# 02_INTERFACE.net
KiCad netlist of a schematic drawn in Altium Designer
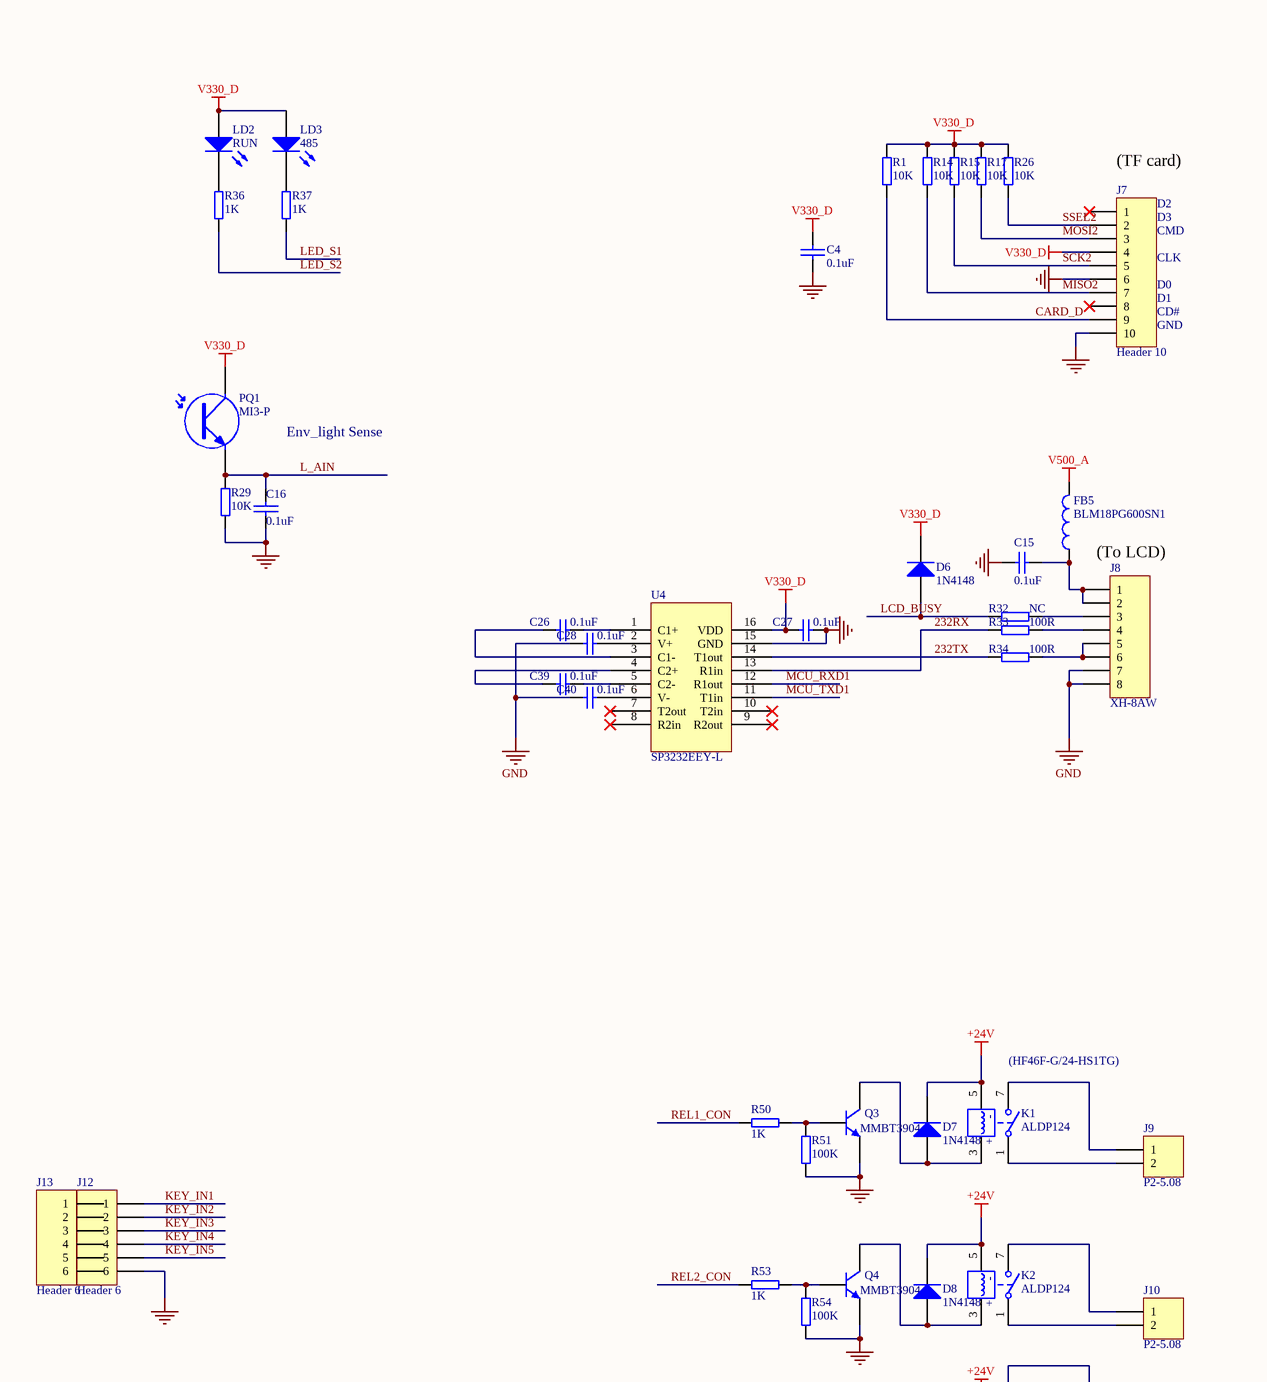
[diagram p0: 02_INTERFACE.SchDoc, top left]
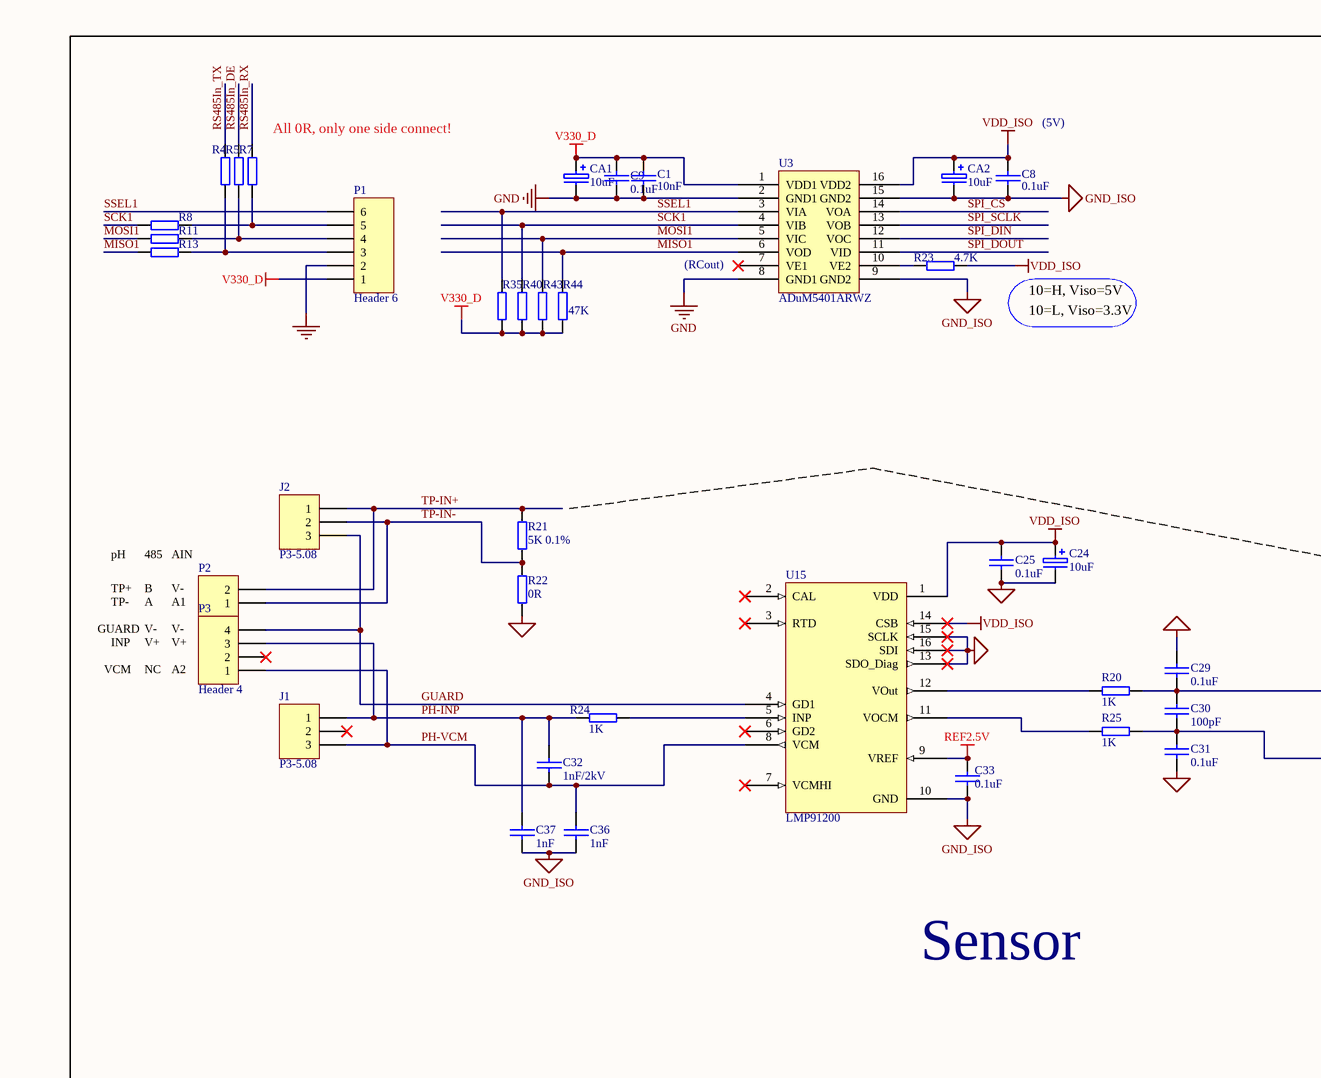
[diagram p1: 02_INTERFACE.SchDoc, top middle]
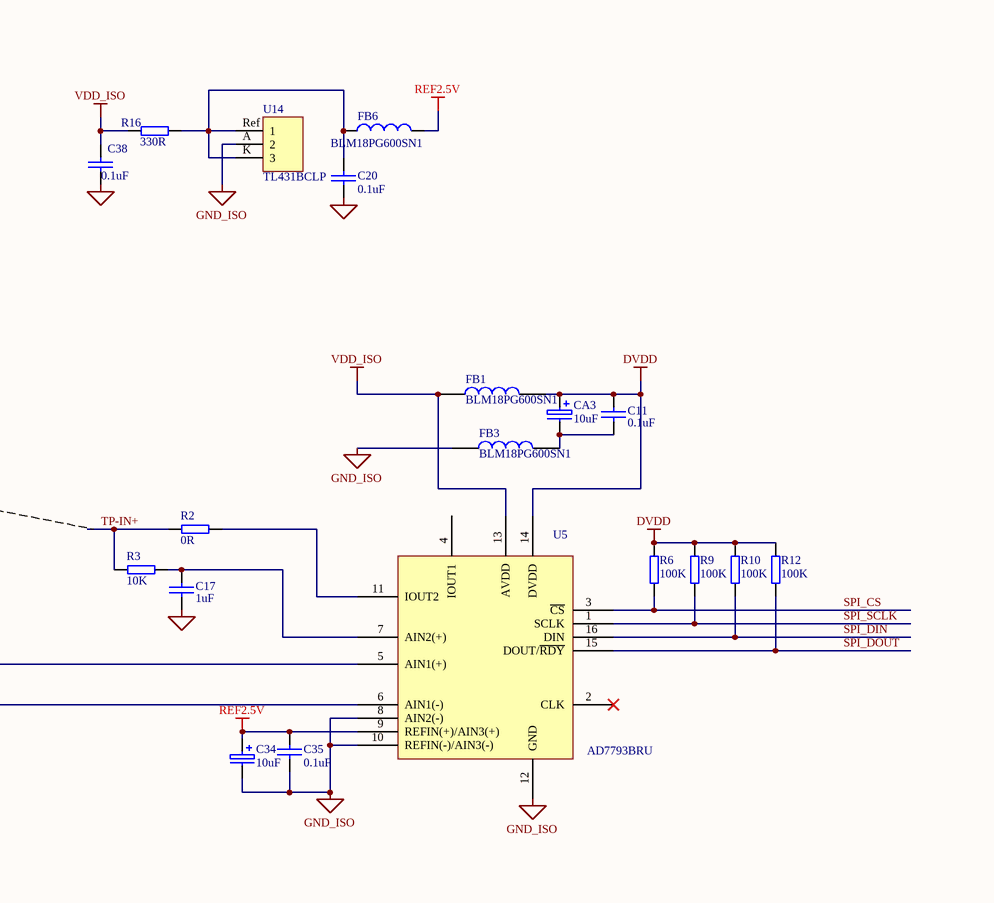
[diagram p2: 02_INTERFACE.SchDoc, top right]
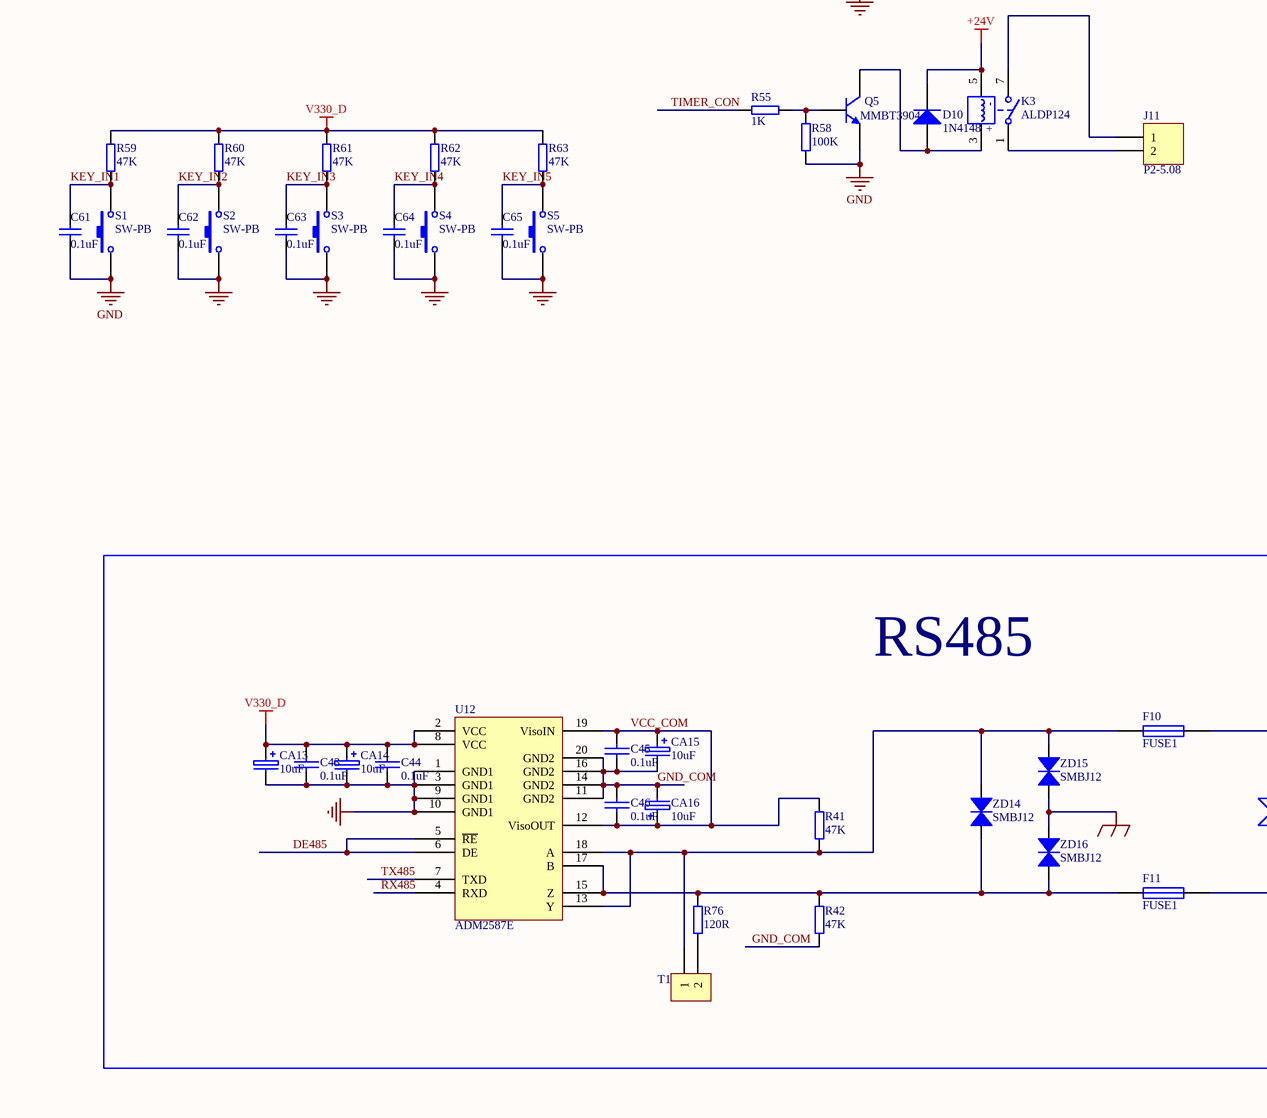
[diagram p3: 02_INTERFACE.SchDoc, bottom left]
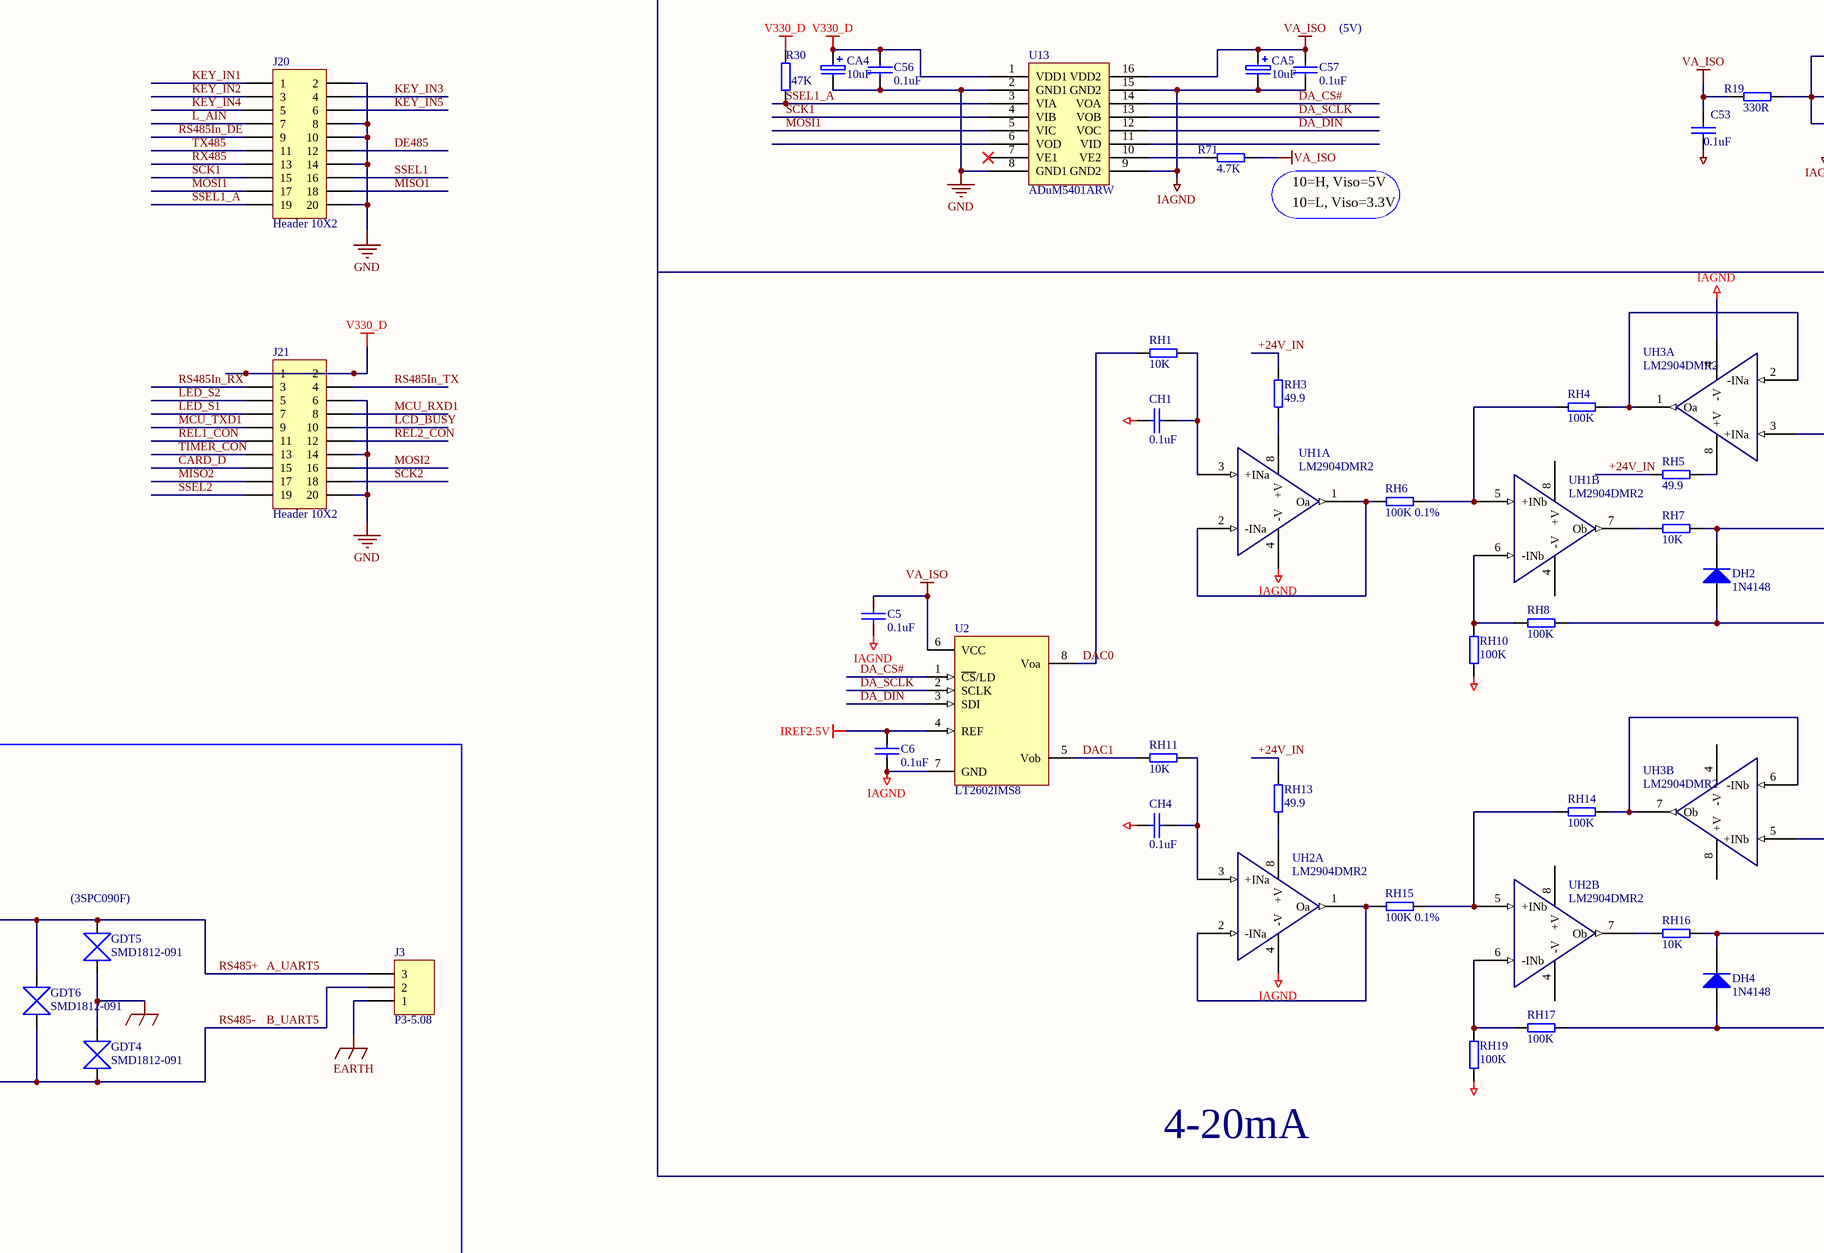
[diagram p4: 02_INTERFACE.SchDoc, bottom middle]
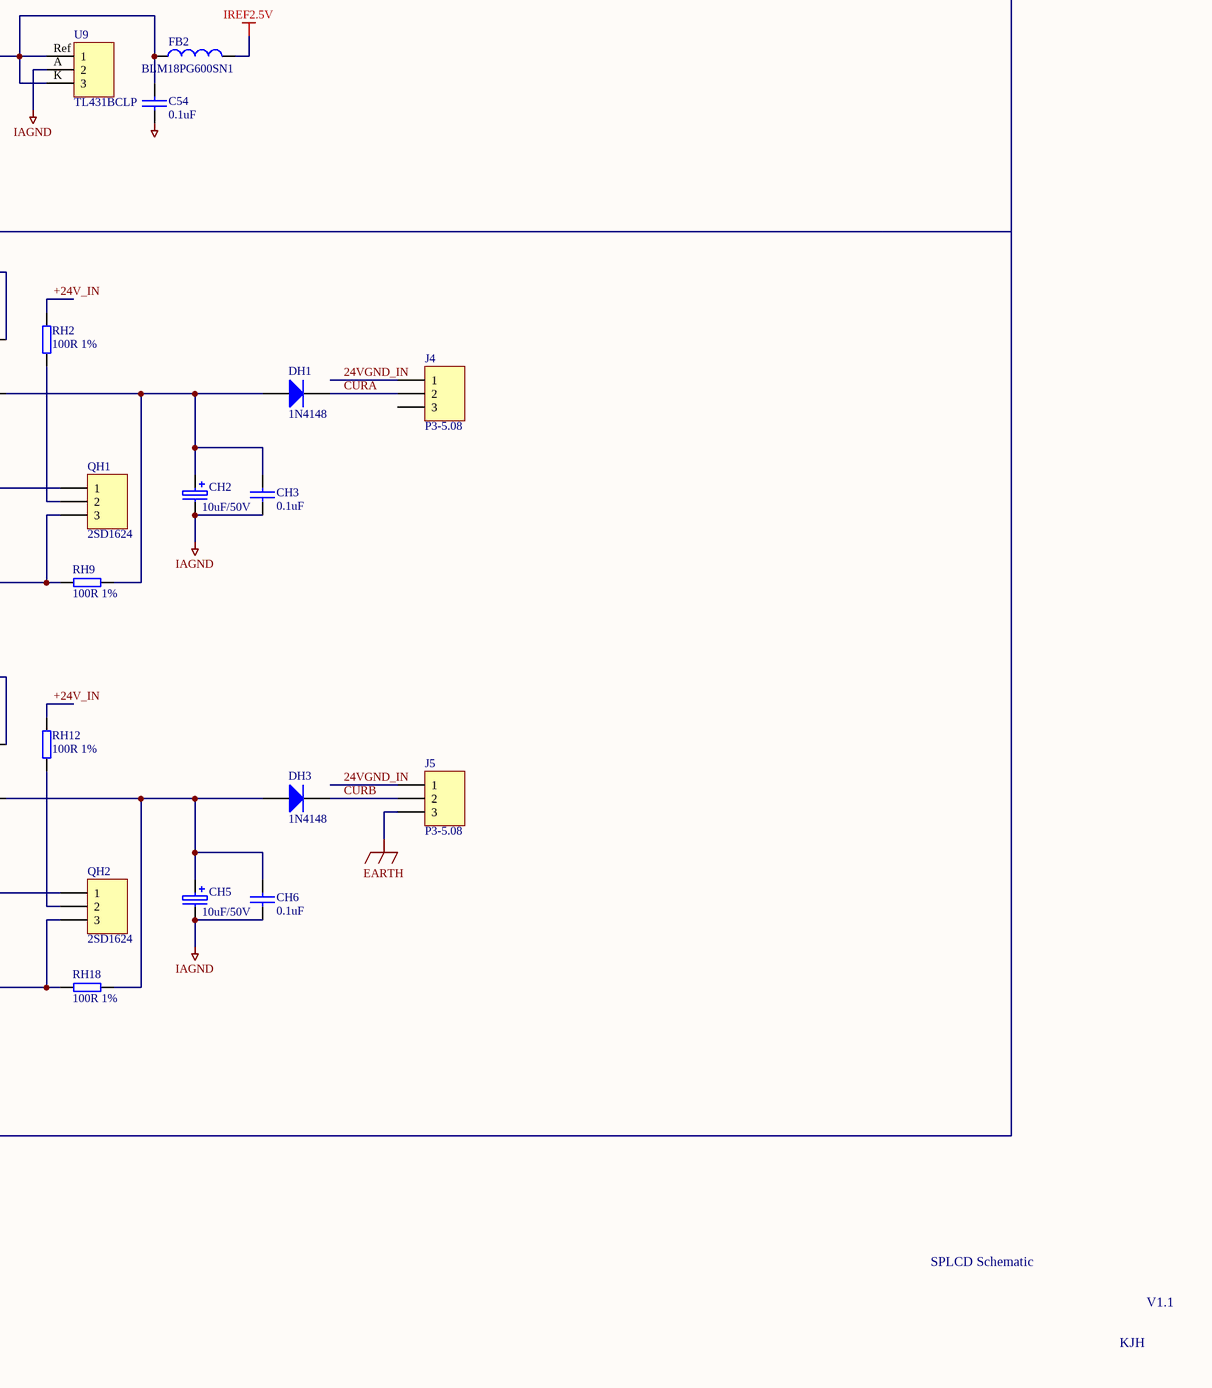
[diagram p5: 02_INTERFACE.SchDoc, bottom right]

(export (version "E")
  (design (tool "Eeschema 10.0.6"))
  (components
    (comp (ref "C1")
      (value "10nF")
      (footprint "0603A")
      (description "电容")
      (libsource (lib "") (part "CAP_1"))
    )
    (comp (ref "C4")
      (value "0.1uF")
      (footprint "0603A")
      (description "Capacitor")
      (libsource (lib "*") (part "CAP"))
    )
    (comp (ref "C5")
      (value "0.1uF")
      (footprint "0603A")
      (description "Capacitor")
      (libsource (lib "*") (part "CAP"))
    )
    (comp (ref "C6")
      (value "0.1uF")
      (footprint "0603A")
      (description "Capacitor")
      (libsource (lib "*") (part "CAP"))
    )
    (comp (ref "C8")
      (value "0.1uF")
      (footprint "0603A")
      (description "电容")
      (libsource (lib "") (part "CAP_1"))
    )
    (comp (ref "C9")
      (value "0.1uF")
      (footprint "0603A")
      (description "电容")
      (libsource (lib "") (part "CAP_1"))
    )
    (comp (ref "C11")
      (value "0.1uF")
      (footprint "0603A")
      (description "电容")
      (libsource (lib "") (part "CAP_1"))
    )
    (comp (ref "C15")
      (value "0.1uF")
      (footprint "0603A")
      (description "Capacitor, X7R Ceramic")
      (libsource (lib "Miscellaneous Devices") (part "Cap"))
    )
    (comp (ref "C16")
      (value "0.1uF")
      (footprint "0603")
      (description "Capacitor")
      (libsource (lib "*") (part "CAP"))
    )
    (comp (ref "C17")
      (value "1uF")
      (footprint "0603A")
      (description "电容")
      (libsource (lib "") (part "CAP_1"))
    )
    (comp (ref "C20")
      (value "0.1uF")
      (footprint "0603A")
      (description "Capacitor")
      (libsource (lib "*") (part "CAP"))
    )
    (comp (ref "C24")
      (value "10uF")
      (footprint "1206")
      (description "极性电容")
      (libsource (lib "*") (part "CAPE"))
    )
    (comp (ref "C25")
      (value "0.1uF")
      (footprint "0603A")
      (description "Capacitor")
      (libsource (lib "*") (part "CAP"))
    )
    (comp (ref "C26")
      (value "0.1uF")
      (footprint "0603A")
      (description "'Capacitor, X7R Ceramic")
      (libsource (lib "Miscellaneous Devices") (part "Cap"))
    )
    (comp (ref "C27")
      (value "0.1uF")
      (footprint "0603A")
      (description "'Capacitor, X7R Ceramic")
      (libsource (lib "Miscellaneous Devices") (part "Cap"))
    )
    (comp (ref "C28")
      (value "0.1uF")
      (footprint "0603A")
      (description "'Capacitor, X7R Ceramic")
      (libsource (lib "Miscellaneous Devices") (part "Cap"))
    )
    (comp (ref "C29")
      (value "0.1uF")
      (footprint "0603A")
      (description "Capacitor")
      (libsource (lib "*") (part "CAP"))
    )
    (comp (ref "C30")
      (value "100pF")
      (footprint "0603A")
      (description "Capacitor")
      (libsource (lib "*") (part "CAP"))
    )
    (comp (ref "C31")
      (value "0.1uF")
      (footprint "0603A")
      (description "Capacitor")
      (libsource (lib "*") (part "CAP"))
    )
    (comp (ref "C32")
      (value "1nF/2kV")
      (footprint "RAD-0.2")
      (description "Capacitor")
      (libsource (lib "*") (part "CAP"))
    )
    (comp (ref "C33")
      (value "0.1uF")
      (footprint "0603A")
      (description "Capacitor")
      (libsource (lib "*") (part "CAP"))
    )
    (comp (ref "C34")
      (value "10uF")
      (footprint "1206")
      (description "极性电容")
      (libsource (lib "*") (part "CAPE"))
    )
    (comp (ref "C35")
      (value "0.1uF")
      (footprint "0603A")
      (description "Capacitor")
      (libsource (lib "*") (part "CAP"))
    )
    (comp (ref "C36")
      (value "1nF")
      (footprint "0603A")
      (description "Capacitor")
      (libsource (lib "*") (part "CAP"))
    )
    (comp (ref "C37")
      (value "1nF")
      (footprint "0603A")
      (description "Capacitor")
      (libsource (lib "*") (part "CAP"))
    )
    (comp (ref "C38")
      (value "0.1uF")
      (footprint "0603A")
      (description "Capacitor")
      (libsource (lib "*") (part "CAP"))
    )
    (comp (ref "C39")
      (value "0.1uF")
      (footprint "0603A")
      (description "'Capacitor, X7R Ceramic")
      (libsource (lib "Miscellaneous Devices") (part "Cap"))
    )
    (comp (ref "C40")
      (value "0.1uF")
      (footprint "0603A")
      (description "'Capacitor, X7R Ceramic")
      (libsource (lib "Miscellaneous Devices") (part "Cap"))
    )
    (comp (ref "C43")
      (value "0.1uF")
      (footprint "0603")
      (description "电容")
      (libsource (lib "") (part "CAP_1"))
    )
    (comp (ref "C44")
      (value "0.1uF")
      (footprint "0603")
      (description "电容")
      (libsource (lib "") (part "CAP_1"))
    )
    (comp (ref "C45")
      (value "0.1uF")
      (footprint "0603")
      (description "电容")
      (libsource (lib "") (part "CAP_1"))
    )
    (comp (ref "C46")
      (value "0.1uF")
      (footprint "0603")
      (description "电容")
      (libsource (lib "") (part "CAP_1"))
    )
    (comp (ref "C53")
      (value "0.1uF")
      (footprint "0603A")
      (description "Capacitor")
      (libsource (lib "*") (part "CAP"))
    )
    (comp (ref "C54")
      (value "0.1uF")
      (footprint "0603A")
      (description "Capacitor")
      (libsource (lib "*") (part "CAP"))
    )
    (comp (ref "C56")
      (value "0.1uF")
      (footprint "0603A")
      (description "Capacitor")
      (libsource (lib "*") (part "CAP"))
    )
    (comp (ref "C57")
      (value "0.1uF")
      (footprint "0603A")
      (description "Capacitor")
      (libsource (lib "*") (part "CAP"))
    )
    (comp (ref "C61")
      (value "0.1uF")
      (footprint "0603A")
      (description "Capacitor, X7R Ceramic")
      (libsource (lib "Miscellaneous Devices") (part "Cap"))
    )
    (comp (ref "C62")
      (value "0.1uF")
      (footprint "0603A")
      (description "Capacitor, X7R Ceramic")
      (libsource (lib "Miscellaneous Devices") (part "Cap"))
    )
    (comp (ref "C63")
      (value "0.1uF")
      (footprint "0603A")
      (description "Capacitor, X7R Ceramic")
      (libsource (lib "Miscellaneous Devices") (part "Cap"))
    )
    (comp (ref "C64")
      (value "0.1uF")
      (footprint "0603A")
      (description "Capacitor, X7R Ceramic")
      (libsource (lib "Miscellaneous Devices") (part "Cap"))
    )
    (comp (ref "C65")
      (value "0.1uF")
      (footprint "0603A")
      (description "Capacitor, X7R Ceramic")
      (libsource (lib "Miscellaneous Devices") (part "Cap"))
    )
    (comp (ref "CA1")
      (value "10uF")
      (footprint "1206")
      (description "极性电容")
      (libsource (lib "*") (part "CAPE"))
    )
    (comp (ref "CA2")
      (value "10uF")
      (footprint "1206")
      (description "极性电容")
      (libsource (lib "*") (part "CAPE"))
    )
    (comp (ref "CA3")
      (value "10uF")
      (footprint "1206")
      (description "极性电容")
      (libsource (lib "*") (part "CAPE"))
    )
    (comp (ref "CA4")
      (value "10uF")
      (footprint "1206")
      (description "极性电容")
      (libsource (lib "*") (part "CAPE"))
    )
    (comp (ref "CA5")
      (value "10uF")
      (footprint "1206C")
      (description "极性电容")
      (libsource (lib "*") (part "CAPE"))
    )
    (comp (ref "CA13")
      (value "10uF")
      (footprint "1206C")
      (description "极性电容")
      (libsource (lib "*") (part "CAPE"))
    )
    (comp (ref "CA14")
      (value "10uF")
      (footprint "1206C")
      (description "极性电容")
      (libsource (lib "*") (part "CAPE"))
    )
    (comp (ref "CA15")
      (value "10uF")
      (footprint "1206C")
      (description "极性电容")
      (libsource (lib "*") (part "CAPE"))
    )
    (comp (ref "CA16")
      (value "10uF")
      (footprint "1206C")
      (description "极性电容")
      (libsource (lib "*") (part "CAPE"))
    )
    (comp (ref "CH1")
      (value "0.1uF")
      (footprint "0603A")
      (description "Capacitor")
      (libsource (lib "*") (part "CAP"))
    )
    (comp (ref "CH2")
      (value "10uF/50V")
      (footprint "1206")
      (description "极性电容")
      (libsource (lib "*") (part "CAPE"))
    )
    (comp (ref "CH3")
      (value "0.1uF")
      (footprint "0603A")
      (description "Capacitor")
      (libsource (lib "*") (part "CAP"))
    )
    (comp (ref "CH4")
      (value "0.1uF")
      (footprint "0603A")
      (description "Capacitor")
      (libsource (lib "*") (part "CAP"))
    )
    (comp (ref "CH5")
      (value "10uF/50V")
      (footprint "1206")
      (description "极性电容")
      (libsource (lib "*") (part "CAPE"))
    )
    (comp (ref "CH6")
      (value "0.1uF")
      (footprint "0603A")
      (description "Capacitor")
      (libsource (lib "*") (part "CAP"))
    )
    (comp (ref "D6")
      (value "1N4148")
      (footprint "1206")
      (description "High Conductance Fast Diode")
      (fields (field (name "PUBLISHER") "Altium Limited"))
      (libsource (lib "Miscellaneous Devices") (part "Diode 1N4148"))
    )
    (comp (ref "D7")
      (value "1N4148")
      (footprint "1206")
      (description "High Conductance Fast Diode")
      (fields (field (name "PUBLISHER") "Altium Limited"))
      (libsource (lib "Miscellaneous Devices") (part "Diode 1N4148"))
    )
    (comp (ref "D8")
      (value "1N4148")
      (footprint "1206")
      (description "High Conductance Fast Diode")
      (fields (field (name "PUBLISHER") "Altium Limited"))
      (libsource (lib "Miscellaneous Devices") (part "Diode 1N4148"))
    )
    (comp (ref "D10")
      (value "1N4148")
      (footprint "1206")
      (description "High Conductance Fast Diode")
      (fields (field (name "PUBLISHER") "Altium Limited"))
      (libsource (lib "Miscellaneous Devices") (part "Diode 1N4148"))
    )
    (comp (ref "DH1")
      (value "1N4148")
      (footprint "1206D")
      (description "1 Amp General Purpose Rectifier")
      (fields (field (name "PUBLISHER") "Altium Limited"))
      (libsource (lib "Miscellaneous Devices") (part "Diode 1N4001"))
    )
    (comp (ref "DH2")
      (value "1N4148")
      (footprint "1206D")
      (description "1 Amp General Purpose Rectifier")
      (fields (field (name "PUBLISHER") "Altium Limited"))
      (libsource (lib "Miscellaneous Devices") (part "Diode 1N4001"))
    )
    (comp (ref "DH3")
      (value "1N4148")
      (footprint "1206D")
      (description "1 Amp General Purpose Rectifier")
      (fields (field (name "PUBLISHER") "Altium Limited"))
      (libsource (lib "Miscellaneous Devices") (part "Diode 1N4001"))
    )
    (comp (ref "DH4")
      (value "1N4148")
      (footprint "1206D")
      (description "1 Amp General Purpose Rectifier")
      (fields (field (name "PUBLISHER") "Altium Limited"))
      (libsource (lib "Miscellaneous Devices") (part "Diode 1N4001"))
    )
    (comp (ref "F10")
      (value "FUSE1")
      (footprint "1206")
      (description "Fuse")
      (libsource (lib "*") (part "FUSE1"))
    )
    (comp (ref "F11")
      (value "FUSE1")
      (footprint "1206")
      (description "Fuse")
      (libsource (lib "*") (part "FUSE1"))
    )
    (comp (ref "FB1") (value "BLM18PG600SN1") (footprint "0603A") (libsource (lib "*") (part "INDUCTOR")))
    (comp (ref "FB2")
      (value "BLM18PG600SN1")
      (footprint "0603A")
      (description "Inductor")
      (fields (field (name "PUBLISHER") "Altium Limited"))
      (libsource (lib "Miscellaneous Devices") (part "Inductor"))
    )
    (comp (ref "FB3") (value "BLM18PG600SN1") (footprint "0603A") (libsource (lib "*") (part "INDUCTOR")))
    (comp (ref "FB5")
      (value "BLM18PG600SN1")
      (footprint "0603A")
      (description "Inductor")
      (fields (field (name "PUBLISHER") "Altium Limited"))
      (libsource (lib "Miscellaneous Devices") (part "Inductor"))
    )
    (comp (ref "FB6")
      (value "BLM18PG600SN1")
      (footprint "0603A")
      (description "Inductor")
      (fields (field (name "PUBLISHER") "Altium Limited"))
      (libsource (lib "Miscellaneous Devices") (part "Inductor"))
    )
    (comp (ref "GDT4") (value "SMD1812-091") (footprint "1812") (libsource (lib "*") (part "BT90")))
    (comp (ref "GDT5") (value "SMD1812-091") (footprint "1812") (libsource (lib "*") (part "BT90")))
    (comp (ref "GDT6") (value "SMD1812-091") (footprint "1812") (libsource (lib "*") (part "BT90")))
    (comp (ref "J1")
      (value "P3-5.08")
      (footprint "PH3-5.08mm")
      (description "Header, 3-Pin")
      (fields (field (name "PUBLISHER") "Altium Limited"))
      (libsource (lib "Miscellaneous Connectors") (part "Header 3"))
    )
    (comp (ref "J2")
      (value "P3-5.08")
      (footprint "PH3-5.08mm")
      (description "Header, 3-Pin")
      (fields (field (name "PUBLISHER") "Altium Limited"))
      (libsource (lib "Miscellaneous Connectors") (part "Header 3"))
    )
    (comp (ref "J3")
      (value "P3-5.08")
      (footprint "PH3-5.08mm")
      (description "Header, 3-Pin")
      (fields (field (name "PUBLISHER") "Altium Limited"))
      (libsource (lib "") (part "Header 3_2"))
    )
    (comp (ref "J4")
      (value "P3-5.08")
      (footprint "PH3-5.08mm")
      (description "Header, 3-Pin")
      (fields (field (name "PUBLISHER") "Altium Limited"))
      (libsource (lib "") (part "Header 3_1"))
    )
    (comp (ref "J5")
      (value "P3-5.08")
      (footprint "PH3-5.08mm")
      (description "Header, 3-Pin")
      (fields (field (name "PUBLISHER") "Altium Limited"))
      (libsource (lib "") (part "Header 3_1"))
    )
    (comp (ref "J7")
      (value "Header 10")
      (footprint "TF Socket")
      (description "Header, 10-Pin")
      (fields (field (name "PUBLISHER") "Altium Limited"))
      (libsource (lib "Miscellaneous Connectors") (part "Header 10"))
    )
    (comp (ref "J8")
      (value "XH-8AW")
      (footprint "HDR1X8")
      (description "Header, 8-Pin")
      (fields (field (name "PUBLISHER") "Altium Limited"))
      (libsource (lib "Miscellaneous Connectors") (part "Header 8"))
    )
    (comp (ref "J9")
      (value "P2-5.08")
      (footprint "PH2-5.08mm")
      (description "Header, 2-Pin")
      (fields (field (name "PUBLISHER") "Altium Limited"))
      (libsource (lib "Miscellaneous Connectors") (part "Header 2"))
    )
    (comp (ref "J10")
      (value "P2-5.08")
      (footprint "PH2-5.08mm")
      (description "Header, 2-Pin")
      (fields (field (name "PUBLISHER") "Altium Limited"))
      (libsource (lib "Miscellaneous Connectors") (part "Header 2"))
    )
    (comp (ref "J11")
      (value "P2-5.08")
      (footprint "PH2-5.08mm")
      (description "Header, 2-Pin")
      (fields (field (name "PUBLISHER") "Altium Limited"))
      (libsource (lib "Miscellaneous Connectors") (part "Header 2"))
    )
    (comp (ref "J12")
      (value "Header 6")
      (footprint "HDR1X6")
      (description "Header, 6-Pin")
      (fields (field (name "PUBLISHER") "Altium Limited"))
      (libsource (lib "Miscellaneous Connectors") (part "Header 6"))
    )
    (comp (ref "J13")
      (value "Header 6")
      (footprint "HDR1X6")
      (description "Header, 6-Pin")
      (fields (field (name "PUBLISHER") "Altium Limited"))
      (libsource (lib "Miscellaneous Connectors") (part "Header 6"))
    )
    (comp (ref "J20")
      (value "Header 10X2")
      (footprint "HDR2X10")
      (description "Header, 10-Pin, Dual row")
      (fields (field (name "PUBLISHER") "Altium Limited"))
      (libsource (lib "Miscellaneous Connectors") (part "Header 10X2"))
    )
    (comp (ref "J21")
      (value "Header 10X2")
      (footprint "HDR2X10")
      (description "Header, 10-Pin, Dual row")
      (fields (field (name "PUBLISHER") "Altium Limited"))
      (libsource (lib "Miscellaneous Connectors") (part "Header 10X2"))
    )
    (comp (ref "K1")
      (value "ALDP124")
      (footprint "ALDP124")
      (description "24V coil, 5A SPST Relay")
      (libsource (lib "S1A120000_COSMO") (part "S1A120000"))
    )
    (comp (ref "K2")
      (value "ALDP124")
      (footprint "ALDP124")
      (description "24V coil, 5A SPST Relay")
      (libsource (lib "S1A120000_COSMO") (part "S1A120000"))
    )
    (comp (ref "K3")
      (value "ALDP124")
      (footprint "ALDP124")
      (description "24V coil, 5A SPST Relay")
      (libsource (lib "S1A120000_COSMO") (part "S1A120000"))
    )
    (comp (ref "LD2")
      (value "RUN")
      (footprint "LED")
      (description "Typical INFRARED GaAs LED")
      (fields (field (name "PUBLISHER") "Altium Limited"))
      (libsource (lib "Miscellaneous Devices") (part "LED0"))
    )
    (comp (ref "LD3")
      (value "485")
      (footprint "LED")
      (description "Typical INFRARED GaAs LED")
      (fields (field (name "PUBLISHER") "Altium Limited"))
      (libsource (lib "Miscellaneous Devices") (part "LED0"))
    )
    (comp (ref "P1")
      (value "Header 6")
      (footprint "HDR1X6")
      (description "Header, 6-Pin")
      (fields (field (name "PUBLISHER") "Altium Limited"))
      (libsource (lib "") (part "Header 6_1"))
    )
    (comp (ref "P2")
      (value "Header 2")
      (footprint "HDR1X2")
      (description "Header, 2-Pin")
      (fields (field (name "PUBLISHER") "Altium Limited"))
      (libsource (lib "") (part "Header 2_1"))
    )
    (comp (ref "P3")
      (value "Header 4")
      (footprint "HDR1X4")
      (description "Header, 4-Pin")
      (fields (field (name "PUBLISHER") "Altium Limited"))
      (libsource (lib "Miscellaneous Connectors") (part "Header 4"))
    )
    (comp (ref "PQ1")
      (value "MI3-P")
      (footprint "LED")
      (description "NPN Phototransistor")
      (fields (field (name "PUBLISHER") "Altium Limited"))
      (libsource (lib "Miscellaneous Devices") (part "Photo NPN"))
    )
    (comp (ref "Q3")
      (value "MMBT3904")
      (footprint "SOT23_N")
      (description "NPN Switching Transistor")
      (fields (field (name "PUBLISHER") "Altium Limited"))
      (libsource (lib "Philips Discrete BJT - Low Power") (part "MMBT3904"))
    )
    (comp (ref "Q4")
      (value "MMBT3904")
      (footprint "SOT23_N")
      (description "NPN Switching Transistor")
      (fields (field (name "PUBLISHER") "Altium Limited"))
      (libsource (lib "Philips Discrete BJT - Low Power") (part "MMBT3904"))
    )
    (comp (ref "Q5")
      (value "MMBT3904")
      (footprint "SOT23_N")
      (description "NPN Switching Transistor")
      (fields (field (name "PUBLISHER") "Altium Limited"))
      (libsource (lib "Philips Discrete BJT - Low Power") (part "MMBT3904"))
    )
    (comp (ref "QH1")
      (value "2SD1624")
      (footprint "SOT89M")
      (description "Header, 3-Pin")
      (fields (field (name "PUBLISHER") "Altium Limited"))
      (libsource (lib "") (part "Header 3_1"))
    )
    (comp (ref "QH2")
      (value "2SD1624")
      (footprint "SOT89M")
      (description "Header, 3-Pin")
      (fields (field (name "PUBLISHER") "Altium Limited"))
      (libsource (lib "") (part "Header 3_1"))
    )
    (comp (ref "R1") (value "10K") (footprint "0603A") (description "电阻") (libsource (lib "*") (part "RES")))
    (comp (ref "R2") (value "0R") (footprint "0603A") (description "电阻") (libsource (lib "*") (part "RES")))
    (comp (ref "R3") (value "10K") (footprint "0603A") (description "电阻") (libsource (lib "*") (part "RES")))
    (comp (ref "R4") (value "0R") (footprint "0603A") (description "电阻") (libsource (lib "*") (part "RES")))
    (comp (ref "R5") (value "0R") (footprint "0603A") (description "电阻") (libsource (lib "*") (part "RES")))
    (comp (ref "R6") (value "100K") (footprint "0603A") (description "电阻") (libsource (lib "*") (part "RES")))
    (comp (ref "R7") (value "0R") (footprint "0603A") (description "电阻") (libsource (lib "*") (part "RES")))
    (comp (ref "R8") (value "0R") (footprint "0603A") (description "电阻") (libsource (lib "*") (part "RES")))
    (comp (ref "R9") (value "100K") (footprint "0603A") (description "电阻") (libsource (lib "*") (part "RES")))
    (comp (ref "R10")
      (value "100K")
      (footprint "0603A")
      (description "电阻")
      (libsource (lib "*") (part "RES"))
    )
    (comp (ref "R11") (value "0R") (footprint "0603A") (description "电阻") (libsource (lib "*") (part "RES")))
    (comp (ref "R12")
      (value "100K")
      (footprint "0603A")
      (description "电阻")
      (libsource (lib "*") (part "RES"))
    )
    (comp (ref "R13") (value "0R") (footprint "0603A") (description "电阻") (libsource (lib "*") (part "RES")))
    (comp (ref "R14") (value "10K") (footprint "0603A") (description "电阻") (libsource (lib "*") (part "RES")))
    (comp (ref "R15") (value "10K") (footprint "0603A") (description "电阻") (libsource (lib "*") (part "RES")))
    (comp (ref "R16")
      (value "330R")
      (footprint "0603A")
      (description "电阻")
      (libsource (lib "*") (part "RES"))
    )
    (comp (ref "R17") (value "10K") (footprint "0603A") (description "电阻") (libsource (lib "*") (part "RES")))
    (comp (ref "R19")
      (value "330R")
      (footprint "0603A")
      (description "电阻")
      (libsource (lib "*") (part "RES"))
    )
    (comp (ref "R20") (value "1K") (footprint "0603A") (description "电阻") (libsource (lib "*") (part "RES")))
    (comp (ref "R21")
      (value "5K 0.1%")
      (footprint "0603A")
      (description "电阻")
      (libsource (lib "*") (part "RES"))
    )
    (comp (ref "R22") (value "0R") (footprint "0603A") (description "电阻") (libsource (lib "*") (part "RES")))
    (comp (ref "R23")
      (value "4.7K")
      (footprint "0603A")
      (description "电阻")
      (libsource (lib "*") (part "RES"))
    )
    (comp (ref "R24") (value "1K") (footprint "0603A") (description "电阻") (libsource (lib "*") (part "RES")))
    (comp (ref "R25") (value "1K") (footprint "0603A") (description "电阻") (libsource (lib "*") (part "RES")))
    (comp (ref "R26") (value "10K") (footprint "0603A") (description "电阻") (libsource (lib "*") (part "RES")))
    (comp (ref "R29") (value "10K") (footprint "0603A") (description "电阻") (libsource (lib "*") (part "RES")))
    (comp (ref "R30") (value "47K") (footprint "0603A") (description "电阻") (libsource (lib "*") (part "RES")))
    (comp (ref "R32") (value "NC") (footprint "0603A") (description "电阻") (libsource (lib "*") (part "RES")))
    (comp (ref "R33")
      (value "100R")
      (footprint "0603A")
      (description "电阻")
      (libsource (lib "*") (part "RES"))
    )
    (comp (ref "R34")
      (value "100R")
      (footprint "0603A")
      (description "电阻")
      (libsource (lib "*") (part "RES"))
    )
    (comp (ref "R35") (value "47K") (footprint "0603A") (description "电阻") (libsource (lib "*") (part "RES")))
    (comp (ref "R36") (value "1K") (footprint "0603A") (description "电阻") (libsource (lib "*") (part "RES")))
    (comp (ref "R37") (value "1K") (footprint "0603A") (description "电阻") (libsource (lib "*") (part "RES")))
    (comp (ref "R40") (value "47K") (footprint "0603A") (description "电阻") (libsource (lib "*") (part "RES")))
    (comp (ref "R41") (value "47K") (footprint "0603") (description "电阻") (libsource (lib "*") (part "RES")))
    (comp (ref "R42") (value "47K") (footprint "0603") (description "电阻") (libsource (lib "*") (part "RES")))
    (comp (ref "R43") (value "47K") (footprint "0603A") (description "电阻") (libsource (lib "*") (part "RES")))
    (comp (ref "R44") (value "47K") (footprint "0603A") (description "电阻") (libsource (lib "*") (part "RES")))
    (comp (ref "R50") (value "1K") (footprint "0603A") (description "电阻") (libsource (lib "*") (part "RES")))
    (comp (ref "R51")
      (value "100K")
      (footprint "0603A")
      (description "电阻")
      (libsource (lib "*") (part "RES"))
    )
    (comp (ref "R53") (value "1K") (footprint "0603A") (description "电阻") (libsource (lib "*") (part "RES")))
    (comp (ref "R54")
      (value "100K")
      (footprint "0603A")
      (description "电阻")
      (libsource (lib "*") (part "RES"))
    )
    (comp (ref "R55") (value "1K") (footprint "0603A") (description "电阻") (libsource (lib "*") (part "RES")))
    (comp (ref "R58")
      (value "100K")
      (footprint "0603A")
      (description "电阻")
      (libsource (lib "*") (part "RES"))
    )
    (comp (ref "R59") (value "47K") (footprint "0603A") (description "电阻") (libsource (lib "*") (part "RES")))
    (comp (ref "R60") (value "47K") (footprint "0603A") (description "电阻") (libsource (lib "*") (part "RES")))
    (comp (ref "R61") (value "47K") (footprint "0603A") (description "电阻") (libsource (lib "*") (part "RES")))
    (comp (ref "R62") (value "47K") (footprint "0603A") (description "电阻") (libsource (lib "*") (part "RES")))
    (comp (ref "R63") (value "47K") (footprint "0603A") (description "电阻") (libsource (lib "*") (part "RES")))
    (comp (ref "R71")
      (value "4.7K")
      (footprint "0603A")
      (description "电阻")
      (libsource (lib "*") (part "RES"))
    )
    (comp (ref "R76") (value "120R") (footprint "0603") (description "电阻") (libsource (lib "*") (part "RES")))
    (comp (ref "RH1") (value "10K") (footprint "0603A") (description "电阻") (libsource (lib "*") (part "RES")))
    (comp (ref "RH2")
      (value "100R 1%")
      (footprint "0603A")
      (description "电阻")
      (libsource (lib "*") (part "RES"))
    )
    (comp (ref "RH3")
      (value "49.9")
      (footprint "0603A")
      (description "电阻")
      (libsource (lib "*") (part "RES"))
    )
    (comp (ref "RH4")
      (value "100K")
      (footprint "0603A")
      (description "电阻")
      (libsource (lib "*") (part "RES"))
    )
    (comp (ref "RH5")
      (value "49.9")
      (footprint "0603A")
      (description "电阻")
      (libsource (lib "*") (part "RES"))
    )
    (comp (ref "RH6")
      (value "100K 0.1%")
      (footprint "0603A")
      (description "电阻")
      (libsource (lib "*") (part "RES"))
    )
    (comp (ref "RH7")
      (value "10K")
      (footprint "0603A")
      (description "Resistor")
      (libsource (lib "*") (part "RES"))
    )
    (comp (ref "RH8")
      (value "100K")
      (footprint "0603A")
      (description "电阻")
      (libsource (lib "*") (part "RES"))
    )
    (comp (ref "RH9")
      (value "100R 1%")
      (footprint "0603A")
      (description "电阻")
      (libsource (lib "*") (part "RES"))
    )
    (comp (ref "RH10")
      (value "100K")
      (footprint "0603A")
      (description "电阻")
      (libsource (lib "*") (part "RES"))
    )
    (comp (ref "RH11")
      (value "10K")
      (footprint "0603A")
      (description "电阻")
      (libsource (lib "*") (part "RES"))
    )
    (comp (ref "RH12")
      (value "100R 1%")
      (footprint "0603A")
      (description "电阻")
      (libsource (lib "*") (part "RES"))
    )
    (comp (ref "RH13")
      (value "49.9")
      (footprint "0603A")
      (description "电阻")
      (libsource (lib "*") (part "RES"))
    )
    (comp (ref "RH14")
      (value "100K")
      (footprint "0603A")
      (description "电阻")
      (libsource (lib "*") (part "RES"))
    )
    (comp (ref "RH15")
      (value "100K 0.1%")
      (footprint "0603A")
      (description "电阻")
      (libsource (lib "*") (part "RES"))
    )
    (comp (ref "RH16")
      (value "10K")
      (footprint "0603A")
      (description "Resistor")
      (libsource (lib "*") (part "RES"))
    )
    (comp (ref "RH17")
      (value "100K")
      (footprint "0603A")
      (description "电阻")
      (libsource (lib "*") (part "RES"))
    )
    (comp (ref "RH18")
      (value "100R 1%")
      (footprint "0603A")
      (description "电阻")
      (libsource (lib "*") (part "RES"))
    )
    (comp (ref "RH19")
      (value "100K")
      (footprint "0603A")
      (description "电阻")
      (libsource (lib "*") (part "RES"))
    )
    (comp (ref "S1")
      (value "SW-PB")
      (description "Switch")
      (fields (field (name "PUBLISHER") "Altium Limited"))
      (libsource (lib "Miscellaneous Devices") (part "SW-PB"))
    )
    (comp (ref "S2")
      (value "SW-PB")
      (description "Switch")
      (fields (field (name "PUBLISHER") "Altium Limited"))
      (libsource (lib "Miscellaneous Devices") (part "SW-PB"))
    )
    (comp (ref "S3")
      (value "SW-PB")
      (description "Switch")
      (fields (field (name "PUBLISHER") "Altium Limited"))
      (libsource (lib "Miscellaneous Devices") (part "SW-PB"))
    )
    (comp (ref "S4")
      (value "SW-PB")
      (description "Switch")
      (fields (field (name "PUBLISHER") "Altium Limited"))
      (libsource (lib "Miscellaneous Devices") (part "SW-PB"))
    )
    (comp (ref "S5")
      (value "SW-PB")
      (description "Switch")
      (fields (field (name "PUBLISHER") "Altium Limited"))
      (libsource (lib "Miscellaneous Devices") (part "SW-PB"))
    )
    (comp (ref "T1")
      (value "~")
      (footprint "SIP2")
      (description "Connector")
      (libsource (lib "*") (part "CON2"))
    )
    (comp (ref "U2") (value "LT2602IMS8") (footprint "LT2602") (libsource (lib "SP1100RS") (part "LT2602")))
    (comp (ref "U3")
      (value "ADuM5401ARWZ")
      (footprint "ADUM1401")
      (description "1Mbps Data Rate, 100ns Propagation delay")
      (libsource (lib "*") (part "ADUM1401"))
    )
    (comp (ref "U4")
      (value "SP3232EEY-L")
      (footprint "TSSOP-16")
      (description "EXAR")
      (libsource (lib "Sch【库】") (part "SP3232EEN"))
    )
    (comp (ref "U5") (value "AD7793BRU") (footprint "AD7793") (libsource (lib "*") (part "AD7793")))
    (comp (ref "U9")
      (value "TL431BCLP")
      (footprint "HDR1X3")
      (description "Programmable Precision Reference")
      (fields (field (name "PUBLISHER") "Altium Limited"))
      (libsource (lib "") (part "Header 3_1"))
    )
    (comp (ref "U12") (value "ADM2587E") (footprint "SOL-20") (libsource (lib "*") (part "ADM2587E")))
    (comp (ref "U13")
      (value "ADuM5401ARW")
      (footprint "ADUM1401")
      (description "1Mbps Data Rate, 100ns Propagation delay")
      (libsource (lib "*") (part "ADUM1401"))
    )
    (comp (ref "U14")
      (value "TL431BCLP")
      (footprint "HDR1X3")
      (description "Programmable Precision Reference")
      (fields (field (name "PUBLISHER") "Altium Limited"))
      (libsource (lib "") (part "Header 3_1"))
    )
    (comp (ref "U15") (value "LMP91200") (footprint "LMP91200") (libsource (lib "*") (part "LMP91200")))
    (comp (ref "UH1") (value "LM2904DMR2") (footprint "SO8_M") (libsource (lib "*") (part "AD8646")))
    (comp (ref "UH2") (value "LM2904DMR2") (footprint "SO8_M") (libsource (lib "*") (part "AD8646")))
    (comp (ref "UH3") (value "LM2904DMR2") (footprint "SO8_M") (libsource (lib "*") (part "AD8646")))
    (comp (ref "ZD14")
      (value "SMBJ12")
      (footprint "ZD")
      (description "瞬变抑制二极管")
      (libsource (lib "*") (part "SMBJ"))
    )
    (comp (ref "ZD15")
      (value "SMBJ12")
      (footprint "ZD")
      (description "瞬变抑制二极管")
      (libsource (lib "*") (part "SMBJ"))
    )
    (comp (ref "ZD16")
      (value "SMBJ12")
      (footprint "ZD")
      (description "瞬变抑制二极管")
      (libsource (lib "*") (part "SMBJ"))
    )
  )
  (nets
    (net (code "1") (name "+24V") (class "Default")
      (node (ref "D10") (pin "2") (pinfunction "K_2") (pintype "passive"))
      (node (ref "D7") (pin "2") (pinfunction "K_2") (pintype "passive"))
      (node (ref "D8") (pin "2") (pinfunction "K_2") (pintype "passive"))
      (node (ref "K1") (pin "5") (pintype "passive"))
      (node (ref "K2") (pin "5") (pintype "passive"))
      (node (ref "K3") (pin "5") (pintype "passive"))
    )
    (net (code "2") (name "/+24V_IN") (class "Default")
      (node (ref "RH12") (pin "1") (pintype "passive"))
      (node (ref "RH13") (pin "1") (pintype "passive"))
      (node (ref "RH2") (pin "1") (pintype "passive"))
      (node (ref "RH3") (pin "1") (pintype "passive"))
      (node (ref "RH5") (pin "1") (pintype "passive"))
    )
    (net (code "3") (name "/24VGND_IN") (class "Default")
      (node (ref "J4") (pin "1") (pinfunction "1_1") (pintype "passive"))
      (node (ref "J5") (pin "1") (pinfunction "1_1") (pintype "passive"))
    )
    (net (code "4") (name "/232RX") (class "Default")
      (node (ref "R33") (pin "2") (pintype "passive"))
      (node (ref "U4") (pin "13") (pinfunction "R1in_13") (pintype "passive"))
    )
    (net (code "5") (name "/232TX") (class "Default")
      (node (ref "R34") (pin "2") (pintype "passive"))
      (node (ref "U4") (pin "14") (pinfunction "T1out_14") (pintype "passive"))
    )
    (net (code "6") (name "/A_UART5") (class "Default")
      (node (ref "F10") (pin "2") (pinfunction "2_2") (pintype "passive"))
      (node (ref "GDT5") (pin "2") (pintype "passive"))
      (node (ref "GDT6") (pin "2") (pintype "passive"))
      (node (ref "J3") (pin "3") (pinfunction "3_3") (pintype "passive"))
    )
    (net (code "7") (name "/B_UART5") (class "Default")
      (node (ref "F11") (pin "2") (pinfunction "2_2") (pintype "passive"))
      (node (ref "GDT4") (pin "1") (pintype "passive"))
      (node (ref "GDT6") (pin "1") (pintype "passive"))
      (node (ref "J3") (pin "2") (pinfunction "2_2") (pintype "passive"))
    )
    (net (code "8") (name "/CARD_D") (class "Default")
      (node (ref "J21") (pin "15") (pinfunction "15_15") (pintype "passive"))
      (node (ref "J7") (pin "9") (pinfunction "9_9") (pintype "passive"))
      (node (ref "R1") (pin "1") (pintype "passive"))
    )
    (net (code "9") (name "/CURA") (class "Default")
      (node (ref "DH1") (pin "2") (pinfunction "K_2") (pintype "passive"))
      (node (ref "J4") (pin "2") (pinfunction "2_2") (pintype "passive"))
    )
    (net (code "10") (name "/CURB") (class "Default")
      (node (ref "DH3") (pin "2") (pinfunction "K_2") (pintype "passive"))
      (node (ref "J5") (pin "2") (pinfunction "2_2") (pintype "passive"))
    )
    (net (code "11") (name "/DAC0") (class "Default")
      (node (ref "RH1") (pin "2") (pintype "passive"))
      (node (ref "U2") (pin "8") (pinfunction "Voa_8") (pintype "passive"))
    )
    (net (code "12") (name "/DAC1") (class "Default")
      (node (ref "RH11") (pin "2") (pintype "passive"))
      (node (ref "U2") (pin "5") (pinfunction "Vob_5") (pintype "passive"))
    )
    (net (code "13") (name "/DA_CS#") (class "Default")
      (node (ref "U13") (pin "14") (pinfunction "VOA_14") (pintype "passive"))
      (node (ref "U2") (pin "1") (pinfunction "~{CS}/LD_1") (pintype "input"))
    )
    (net (code "14") (name "/DA_DIN") (class "Default")
      (node (ref "U13") (pin "12") (pinfunction "VOC_12") (pintype "passive"))
      (node (ref "U2") (pin "3") (pinfunction "SDI_3") (pintype "input"))
    )
    (net (code "15") (name "/DA_SCLK") (class "Default")
      (node (ref "U13") (pin "13") (pinfunction "VOB_13") (pintype "passive"))
      (node (ref "U2") (pin "2") (pinfunction "SCLK_2") (pintype "input"))
    )
    (net (code "16") (name "/DE485") (class "Default")
      (node (ref "J20") (pin "12") (pinfunction "12_12") (pintype "passive"))
      (node (ref "U12") (pin "5") (pinfunction "~{RE}_5") (pintype "passive"))
      (node (ref "U12") (pin "6") (pinfunction "DE_6") (pintype "passive"))
    )
    (net (code "17") (name "/GND_COM") (class "Default")
      (node (ref "C45") (pin "2") (pintype "passive"))
      (node (ref "C46") (pin "1") (pintype "passive"))
      (node (ref "CA15") (pin "2") (pintype "passive"))
      (node (ref "CA16") (pin "2") (pintype "passive"))
      (node (ref "R42") (pin "2") (pintype "passive"))
      (node (ref "U12") (pin "11") (pinfunction "GND2_11") (pintype "passive"))
      (node (ref "U12") (pin "14") (pinfunction "GND2_14") (pintype "passive"))
      (node (ref "U12") (pin "16") (pinfunction "GND2_16") (pintype "passive"))
      (node (ref "U12") (pin "20") (pinfunction "GND2_20") (pintype "passive"))
    )
    (net (code "18") (name "/GUARD") (class "Default")
      (node (ref "J2") (pin "3") (pinfunction "3_3") (pintype "passive"))
      (node (ref "P3") (pin "4") (pinfunction "4_4") (pintype "passive"))
      (node (ref "U15") (pin "4") (pinfunction "GD1_4") (pintype "input"))
    )
    (net (code "19") (name "/KEY_IN1") (class "Default")
      (node (ref "C61") (pin "1") (pinfunction "1_1") (pintype "passive"))
      (node (ref "J12") (pin "1") (pinfunction "1_1") (pintype "passive"))
      (node (ref "J20") (pin "1") (pinfunction "1_1") (pintype "passive"))
      (node (ref "R59") (pin "1") (pintype "passive"))
      (node (ref "S1") (pin "2") (pinfunction "2_2") (pintype "passive"))
    )
    (net (code "20") (name "/KEY_IN2") (class "Default")
      (node (ref "C62") (pin "1") (pinfunction "1_1") (pintype "passive"))
      (node (ref "J12") (pin "2") (pinfunction "2_2") (pintype "passive"))
      (node (ref "J20") (pin "3") (pinfunction "3_3") (pintype "passive"))
      (node (ref "R60") (pin "1") (pintype "passive"))
      (node (ref "S2") (pin "2") (pinfunction "2_2") (pintype "passive"))
    )
    (net (code "21") (name "/KEY_IN3") (class "Default")
      (node (ref "C63") (pin "1") (pinfunction "1_1") (pintype "passive"))
      (node (ref "J12") (pin "3") (pinfunction "3_3") (pintype "passive"))
      (node (ref "J20") (pin "4") (pinfunction "4_4") (pintype "passive"))
      (node (ref "R61") (pin "1") (pintype "passive"))
      (node (ref "S3") (pin "2") (pinfunction "2_2") (pintype "passive"))
    )
    (net (code "22") (name "/KEY_IN4") (class "Default")
      (node (ref "C64") (pin "1") (pinfunction "1_1") (pintype "passive"))
      (node (ref "J12") (pin "4") (pinfunction "4_4") (pintype "passive"))
      (node (ref "J20") (pin "5") (pinfunction "5_5") (pintype "passive"))
      (node (ref "R62") (pin "1") (pintype "passive"))
      (node (ref "S4") (pin "2") (pinfunction "2_2") (pintype "passive"))
    )
    (net (code "23") (name "/KEY_IN5") (class "Default")
      (node (ref "C65") (pin "1") (pinfunction "1_1") (pintype "passive"))
      (node (ref "J12") (pin "5") (pinfunction "5_5") (pintype "passive"))
      (node (ref "J20") (pin "6") (pinfunction "6_6") (pintype "passive"))
      (node (ref "R63") (pin "1") (pintype "passive"))
      (node (ref "S5") (pin "2") (pinfunction "2_2") (pintype "passive"))
    )
    (net (code "24") (name "/LCD_BUSY") (class "Default")
      (node (ref "D6") (pin "1") (pinfunction "A_1") (pintype "passive"))
      (node (ref "J21") (pin "10") (pinfunction "10_10") (pintype "passive"))
      (node (ref "R32") (pin "2") (pintype "passive"))
    )
    (net (code "25") (name "/LED_S1") (class "Default")
      (node (ref "J21") (pin "7") (pinfunction "7_7") (pintype "passive"))
      (node (ref "R37") (pin "1") (pintype "passive"))
    )
    (net (code "26") (name "/LED_S2") (class "Default")
      (node (ref "J21") (pin "5") (pinfunction "5_5") (pintype "passive"))
      (node (ref "R36") (pin "1") (pintype "passive"))
    )
    (net (code "27") (name "/L_AIN") (class "Default")
      (node (ref "C16") (pin "1") (pinfunction "1_1") (pintype "passive"))
      (node (ref "J20") (pin "7") (pinfunction "7_7") (pintype "passive"))
      (node (ref "PQ1") (pin "3") (pinfunction "E_3") (pintype "passive"))
      (node (ref "R29") (pin "2") (pintype "passive"))
    )
    (net (code "28") (name "/MCU_RXD1") (class "Default")
      (node (ref "J21") (pin "8") (pinfunction "8_8") (pintype "passive"))
      (node (ref "U4") (pin "12") (pinfunction "R1out_12") (pintype "passive"))
    )
    (net (code "29") (name "/MCU_TXD1") (class "Default")
      (node (ref "J21") (pin "9") (pinfunction "9_9") (pintype "passive"))
      (node (ref "U4") (pin "11") (pinfunction "T1in_11") (pintype "passive"))
    )
    (net (code "30") (name "/MISO1") (class "Default")
      (node (ref "J20") (pin "18") (pinfunction "18_18") (pintype "passive"))
      (node (ref "R13") (pin "2") (pintype "passive"))
      (node (ref "R44") (pin "2") (pintype "passive"))
      (node (ref "U3") (pin "6") (pinfunction "VOD_6") (pintype "passive"))
    )
    (net (code "31") (name "/MISO2") (class "Default")
      (node (ref "J21") (pin "17") (pinfunction "17_17") (pintype "passive"))
      (node (ref "J7") (pin "7") (pinfunction "7_7") (pintype "passive"))
      (node (ref "R14") (pin "1") (pintype "passive"))
    )
    (net (code "32") (name "/MOSI1") (class "Default")
      (node (ref "J20") (pin "17") (pinfunction "17_17") (pintype "passive"))
      (node (ref "R11") (pin "2") (pintype "passive"))
      (node (ref "R43") (pin "2") (pintype "passive"))
      (node (ref "U13") (pin "5") (pinfunction "VIC_5") (pintype "passive"))
      (node (ref "U3") (pin "5") (pinfunction "VIC_5") (pintype "passive"))
    )
    (net (code "33") (name "/MOSI2") (class "Default")
      (node (ref "J21") (pin "16") (pinfunction "16_16") (pintype "passive"))
      (node (ref "J7") (pin "3") (pinfunction "3_3") (pintype "passive"))
      (node (ref "R17") (pin "1") (pintype "passive"))
    )
    (net (code "34") (name "/PH-INP") (class "Default")
      (node (ref "C32") (pin "1") (pinfunction "1_1") (pintype "passive"))
      (node (ref "C37") (pin "1") (pinfunction "1_1") (pintype "passive"))
      (node (ref "J1") (pin "1") (pinfunction "1_1") (pintype "passive"))
      (node (ref "P3") (pin "3") (pinfunction "3_3") (pintype "passive"))
      (node (ref "R24") (pin "1") (pintype "passive"))
    )
    (net (code "35") (name "/PH-VCM") (class "Default")
      (node (ref "C32") (pin "2") (pinfunction "2_2") (pintype "passive"))
      (node (ref "C36") (pin "1") (pinfunction "1_1") (pintype "passive"))
      (node (ref "J1") (pin "3") (pinfunction "3_3") (pintype "passive"))
      (node (ref "P3") (pin "1") (pinfunction "1_1") (pintype "passive"))
      (node (ref "U15") (pin "8") (pinfunction "VCM_8") (pintype "output"))
    )
    (net (code "36") (name "/REL1_CON") (class "Default")
      (node (ref "J21") (pin "11") (pinfunction "11_11") (pintype "passive"))
      (node (ref "R50") (pin "2") (pintype "passive"))
    )
    (net (code "37") (name "/REL2_CON") (class "Default")
      (node (ref "J21") (pin "12") (pinfunction "12_12") (pintype "passive"))
      (node (ref "R53") (pin "2") (pintype "passive"))
    )
    (net (code "38") (name "/RS485In_DE") (class "Default")
      (node (ref "J20") (pin "9") (pinfunction "9_9") (pintype "passive"))
      (node (ref "R5") (pin "1") (pintype "passive"))
    )
    (net (code "39") (name "/RS485In_RX") (class "Default")
      (node (ref "J21") (pin "3") (pinfunction "3_3") (pintype "passive"))
      (node (ref "R7") (pin "1") (pintype "passive"))
    )
    (net (code "40") (name "/RS485In_TX") (class "Default")
      (node (ref "J21") (pin "4") (pinfunction "4_4") (pintype "passive"))
      (node (ref "R4") (pin "1") (pintype "passive"))
    )
    (net (code "41") (name "/RX485") (class "Default")
      (node (ref "J20") (pin "13") (pinfunction "13_13") (pintype "passive"))
      (node (ref "U12") (pin "4") (pinfunction "RXD_4") (pintype "passive"))
    )
    (net (code "42") (name "/SCK1") (class "Default")
      (node (ref "J20") (pin "15") (pinfunction "15_15") (pintype "passive"))
      (node (ref "R40") (pin "2") (pintype "passive"))
      (node (ref "R8") (pin "2") (pintype "passive"))
      (node (ref "U13") (pin "4") (pinfunction "VIB_4") (pintype "passive"))
      (node (ref "U3") (pin "4") (pinfunction "VIB_4") (pintype "passive"))
    )
    (net (code "43") (name "/SCK2") (class "Default")
      (node (ref "J21") (pin "18") (pinfunction "18_18") (pintype "passive"))
      (node (ref "J7") (pin "5") (pinfunction "5_5") (pintype "passive"))
      (node (ref "R15") (pin "1") (pintype "passive"))
    )
    (net (code "44") (name "/SPI_CS") (class "Default")
      (node (ref "R6") (pin "2") (pintype "passive"))
      (node (ref "U3") (pin "14") (pinfunction "VOA_14") (pintype "passive"))
      (node (ref "U5") (pin "3") (pinfunction "~{CS}_3") (pintype "passive"))
    )
    (net (code "45") (name "/SPI_DIN") (class "Default")
      (node (ref "R10") (pin "2") (pintype "passive"))
      (node (ref "U3") (pin "12") (pinfunction "VOC_12") (pintype "passive"))
      (node (ref "U5") (pin "16") (pinfunction "DIN_16") (pintype "passive"))
    )
    (net (code "46") (name "/SPI_DOUT") (class "Default")
      (node (ref "R12") (pin "2") (pintype "passive"))
      (node (ref "U3") (pin "11") (pinfunction "VID_11") (pintype "passive"))
      (node (ref "U5") (pin "15") (pinfunction "DOUT/~{RDY}_15") (pintype "passive"))
    )
    (net (code "47") (name "/SPI_SCLK") (class "Default")
      (node (ref "R9") (pin "2") (pintype "passive"))
      (node (ref "U3") (pin "13") (pinfunction "VOB_13") (pintype "passive"))
      (node (ref "U5") (pin "1") (pinfunction "SCLK_1") (pintype "passive"))
    )
    (net (code "48") (name "/SSEL1") (class "Default")
      (node (ref "J20") (pin "16") (pinfunction "16_16") (pintype "passive"))
      (node (ref "P1") (pin "6") (pinfunction "6_6") (pintype "passive"))
      (node (ref "R35") (pin "2") (pintype "passive"))
      (node (ref "U3") (pin "3") (pinfunction "VIA_3") (pintype "passive"))
    )
    (net (code "49") (name "/SSEL1_A") (class "Default")
      (node (ref "J20") (pin "19") (pinfunction "19_19") (pintype "passive"))
      (node (ref "R30") (pin "1") (pintype "passive"))
      (node (ref "U13") (pin "3") (pinfunction "VIA_3") (pintype "passive"))
    )
    (net (code "50") (name "/SSEL2") (class "Default")
      (node (ref "J21") (pin "19") (pinfunction "19_19") (pintype "passive"))
      (node (ref "J7") (pin "2") (pinfunction "2_2") (pintype "passive"))
      (node (ref "R26") (pin "1") (pintype "passive"))
    )
    (net (code "51") (name "/TIMER_CON") (class "Default")
      (node (ref "J21") (pin "13") (pinfunction "13_13") (pintype "passive"))
      (node (ref "R55") (pin "2") (pintype "passive"))
    )
    (net (code "52") (name "/TP-IN+") (class "Default")
      (node (ref "J2") (pin "1") (pinfunction "1_1") (pintype "passive"))
      (node (ref "P2") (pin "2") (pinfunction "2_2") (pintype "passive"))
      (node (ref "R2") (pin "1") (pintype "passive"))
      (node (ref "R21") (pin "2") (pintype "passive"))
      (node (ref "R3") (pin "1") (pintype "passive"))
    )
    (net (code "53") (name "/TP-IN-") (class "Default")
      (node (ref "J2") (pin "2") (pinfunction "2_2") (pintype "passive"))
      (node (ref "P2") (pin "1") (pinfunction "1_1") (pintype "passive"))
      (node (ref "R21") (pin "1") (pintype "passive"))
      (node (ref "R22") (pin "1") (pintype "passive"))
    )
    (net (code "54") (name "/TX485") (class "Default")
      (node (ref "J20") (pin "11") (pinfunction "11_11") (pintype "passive"))
      (node (ref "U12") (pin "7") (pinfunction "TXD_7") (pintype "passive"))
    )
    (net (code "55") (name "/VCC_COM") (class "Default")
      (node (ref "C45") (pin "1") (pintype "passive"))
      (node (ref "C46") (pin "2") (pintype "passive"))
      (node (ref "CA15") (pin "1") (pintype "passive"))
      (node (ref "CA16") (pin "1") (pintype "passive"))
      (node (ref "R41") (pin "1") (pintype "passive"))
      (node (ref "U12") (pin "12") (pinfunction "VisoOUT_12") (pintype "passive"))
      (node (ref "U12") (pin "19") (pinfunction "VisoIN_19") (pintype "passive"))
    )
    (net (code "56") (name "DVDD") (class "Default")
      (node (ref "C11") (pin "1") (pintype "passive"))
      (node (ref "CA3") (pin "1") (pintype "passive"))
      (node (ref "FB1") (pin "2") (pinfunction "2_2") (pintype "passive"))
      (node (ref "R10") (pin "1") (pintype "passive"))
      (node (ref "R12") (pin "1") (pintype "passive"))
      (node (ref "R6") (pin "1") (pintype "passive"))
      (node (ref "R9") (pin "1") (pintype "passive"))
      (node (ref "U5") (pin "14") (pinfunction "DVDD_14") (pintype "passive"))
    )
    (net (code "57") (name "EARTH") (class "Default")
      (node (ref "GDT4") (pin "2") (pintype "passive"))
      (node (ref "GDT5") (pin "1") (pintype "passive"))
      (node (ref "J3") (pin "1") (pinfunction "1_1") (pintype "passive"))
      (node (ref "J5") (pin "3") (pinfunction "3_3") (pintype "passive"))
      (node (ref "ZD15") (pin "2") (pintype "passive"))
      (node (ref "ZD16") (pin "1") (pintype "passive"))
    )
    (net (code "58") (name "GND") (class "Default")
      (node (ref "C1") (pin "2") (pintype "passive"))
      (node (ref "C15") (pin "2") (pinfunction "2_2") (pintype "passive"))
      (node (ref "C16") (pin "2") (pinfunction "2_2") (pintype "passive"))
      (node (ref "C27") (pin "1") (pinfunction "1_1") (pintype "passive"))
      (node (ref "C28") (pin "2") (pinfunction "2_2") (pintype "passive"))
      (node (ref "C4") (pin "1") (pinfunction "1_1") (pintype "passive"))
      (node (ref "C40") (pin "2") (pinfunction "2_2") (pintype "passive"))
      (node (ref "C43") (pin "2") (pintype "passive"))
      (node (ref "C44") (pin "2") (pintype "passive"))
      (node (ref "C56") (pin "2") (pinfunction "2_2") (pintype "passive"))
      (node (ref "C61") (pin "2") (pinfunction "2_2") (pintype "passive"))
      (node (ref "C62") (pin "2") (pinfunction "2_2") (pintype "passive"))
      (node (ref "C63") (pin "2") (pinfunction "2_2") (pintype "passive"))
      (node (ref "C64") (pin "2") (pinfunction "2_2") (pintype "passive"))
      (node (ref "C65") (pin "2") (pinfunction "2_2") (pintype "passive"))
      (node (ref "C9") (pin "1") (pintype "passive"))
      (node (ref "CA1") (pin "2") (pintype "passive"))
      (node (ref "CA13") (pin "2") (pintype "passive"))
      (node (ref "CA14") (pin "2") (pintype "passive"))
      (node (ref "CA4") (pin "2") (pintype "passive"))
      (node (ref "J12") (pin "6") (pinfunction "6_6") (pintype "passive"))
      (node (ref "J20") (pin "10") (pinfunction "10_10") (pintype "passive"))
      (node (ref "J20") (pin "14") (pinfunction "14_14") (pintype "passive"))
      (node (ref "J20") (pin "2") (pinfunction "2_2") (pintype "passive"))
      (node (ref "J20") (pin "20") (pinfunction "20_20") (pintype "passive"))
      (node (ref "J20") (pin "8") (pinfunction "8_8") (pintype "passive"))
      (node (ref "J21") (pin "14") (pinfunction "14_14") (pintype "passive"))
      (node (ref "J21") (pin "20") (pinfunction "20_20") (pintype "passive"))
      (node (ref "J21") (pin "6") (pinfunction "6_6") (pintype "passive"))
      (node (ref "J7") (pin "10") (pinfunction "10_10") (pintype "passive"))
      (node (ref "J7") (pin "6") (pinfunction "6_6") (pintype "passive"))
      (node (ref "J8") (pin "7") (pinfunction "7_7") (pintype "passive"))
      (node (ref "J8") (pin "8") (pinfunction "8_8") (pintype "passive"))
      (node (ref "P1") (pin "2") (pinfunction "2_2") (pintype "passive"))
      (node (ref "Q3") (pin "2") (pinfunction "E_2") (pintype "passive"))
      (node (ref "Q4") (pin "2") (pinfunction "E_2") (pintype "passive"))
      (node (ref "Q5") (pin "2") (pinfunction "E_2") (pintype "passive"))
      (node (ref "R29") (pin "1") (pintype "passive"))
      (node (ref "R51") (pin "2") (pintype "passive"))
      (node (ref "R54") (pin "2") (pintype "passive"))
      (node (ref "R58") (pin "2") (pintype "passive"))
      (node (ref "S1") (pin "1") (pinfunction "1_1") (pintype "passive"))
      (node (ref "S2") (pin "1") (pinfunction "1_1") (pintype "passive"))
      (node (ref "S3") (pin "1") (pinfunction "1_1") (pintype "passive"))
      (node (ref "S4") (pin "1") (pinfunction "1_1") (pintype "passive"))
      (node (ref "S5") (pin "1") (pinfunction "1_1") (pintype "passive"))
      (node (ref "U12") (pin "1") (pinfunction "GND1_1") (pintype "passive"))
      (node (ref "U12") (pin "10") (pinfunction "GND1_10") (pintype "passive"))
      (node (ref "U12") (pin "3") (pinfunction "GND1_3") (pintype "passive"))
      (node (ref "U12") (pin "9") (pinfunction "GND1_9") (pintype "passive"))
      (node (ref "U13") (pin "2") (pinfunction "GND1_2") (pintype "passive"))
      (node (ref "U13") (pin "8") (pinfunction "GND1_8") (pintype "passive"))
      (node (ref "U3") (pin "2") (pinfunction "GND1_2") (pintype "passive"))
      (node (ref "U3") (pin "8") (pinfunction "GND1_8") (pintype "passive"))
      (node (ref "U4") (pin "15") (pinfunction "GND_15") (pintype "passive"))
    )
    (net (code "59") (name "GND_ISO") (class "Default")
      (node (ref "C17") (pin "2") (pintype "passive"))
      (node (ref "C20") (pin "2") (pinfunction "2_2") (pintype "passive"))
      (node (ref "C24") (pin "2") (pintype "passive"))
      (node (ref "C25") (pin "2") (pinfunction "2_2") (pintype "passive"))
      (node (ref "C29") (pin "1") (pinfunction "1_1") (pintype "passive"))
      (node (ref "C31") (pin "2") (pinfunction "2_2") (pintype "passive"))
      (node (ref "C33") (pin "2") (pinfunction "2_2") (pintype "passive"))
      (node (ref "C34") (pin "2") (pintype "passive"))
      (node (ref "C35") (pin "2") (pinfunction "2_2") (pintype "passive"))
      (node (ref "C36") (pin "2") (pinfunction "2_2") (pintype "passive"))
      (node (ref "C37") (pin "2") (pinfunction "2_2") (pintype "passive"))
      (node (ref "C38") (pin "2") (pinfunction "2_2") (pintype "passive"))
      (node (ref "C8") (pin "2") (pintype "passive"))
      (node (ref "CA2") (pin "2") (pintype "passive"))
      (node (ref "FB3") (pin "1") (pinfunction "1_1") (pintype "passive"))
      (node (ref "R22") (pin "2") (pintype "passive"))
      (node (ref "U14") (pin "2") (pinfunction "2_2") (pintype "passive"))
      (node (ref "U15") (pin "10") (pinfunction "GND_10") (pintype "power_in"))
      (node (ref "U15") (pin "13") (pinfunction "SDO_Diag_13") (pintype "output"))
      (node (ref "U15") (pin "15") (pinfunction "SCLK_15") (pintype "input"))
      (node (ref "U15") (pin "16") (pinfunction "SDI_16") (pintype "input"))
      (node (ref "U3") (pin "15") (pinfunction "GND2_15") (pintype "passive"))
      (node (ref "U3") (pin "9") (pinfunction "GND2_9") (pintype "passive"))
      (node (ref "U5") (pin "10") (pinfunction "REFIN(-)/AIN3(-)_10") (pintype "passive"))
      (node (ref "U5") (pin "12") (pinfunction "GND_12") (pintype "passive"))
      (node (ref "U5") (pin "8") (pinfunction "AIN2(-)_8") (pintype "passive"))
    )
    (net (code "60") (name "IAGND") (class "Default")
      (node (ref "C5") (pin "2") (pinfunction "2_2") (pintype "passive"))
      (node (ref "C53") (pin "2") (pinfunction "2_2") (pintype "passive"))
      (node (ref "C54") (pin "2") (pinfunction "2_2") (pintype "passive"))
      (node (ref "C57") (pin "2") (pinfunction "2_2") (pintype "passive"))
      (node (ref "C6") (pin "2") (pinfunction "2_2") (pintype "passive"))
      (node (ref "CA5") (pin "2") (pintype "passive"))
      (node (ref "CH1") (pin "1") (pinfunction "1_1") (pintype "passive"))
      (node (ref "CH2") (pin "2") (pintype "passive"))
      (node (ref "CH3") (pin "1") (pinfunction "1_1") (pintype "passive"))
      (node (ref "CH4") (pin "1") (pinfunction "1_1") (pintype "passive"))
      (node (ref "CH5") (pin "2") (pintype "passive"))
      (node (ref "CH6") (pin "1") (pinfunction "1_1") (pintype "passive"))
      (node (ref "RH10") (pin "2") (pintype "passive"))
      (node (ref "RH19") (pin "2") (pintype "passive"))
      (node (ref "U13") (pin "15") (pinfunction "GND2_15") (pintype "passive"))
      (node (ref "U13") (pin "9") (pinfunction "GND2_9") (pintype "passive"))
      (node (ref "U2") (pin "7") (pinfunction "GND_7") (pintype "power_in"))
      (node (ref "U9") (pin "2") (pinfunction "2_2") (pintype "passive"))
      (node (ref "UH1") (pin "4") (pinfunction "-V_4") (pintype "power_in"))
      (node (ref "UH2") (pin "4") (pinfunction "-V_4") (pintype "power_in"))
      (node (ref "UH3") (pin "4") (pinfunction "-V_4") (pintype "power_in"))
    )
    (net (code "61") (name "IREF2.5V") (class "Default")
      (node (ref "C6") (pin "1") (pinfunction "1_1") (pintype "passive"))
      (node (ref "FB2") (pin "2") (pinfunction "2_2") (pintype "passive"))
      (node (ref "U2") (pin "4") (pinfunction "REF_4") (pintype "input"))
    )
    (net (code "62") (name "Net-(C11-Pad2)") (class "Default")
      (node (ref "C11") (pin "2") (pintype "passive"))
      (node (ref "CA3") (pin "2") (pintype "passive"))
      (node (ref "FB3") (pin "2") (pinfunction "2_2") (pintype "passive"))
    )
    (net (code "63") (name "Net-(C15-Pad1)") (class "Default")
      (node (ref "C15") (pin "1") (pinfunction "1_1") (pintype "passive"))
      (node (ref "FB5") (pin "1") (pinfunction "1_1") (pintype "passive"))
      (node (ref "J8") (pin "1") (pinfunction "1_1") (pintype "passive"))
      (node (ref "J8") (pin "2") (pinfunction "2_2") (pintype "passive"))
    )
    (net (code "64") (name "Net-(C20-Pad1)") (class "Default")
      (node (ref "C20") (pin "1") (pinfunction "1_1") (pintype "passive"))
      (node (ref "FB6") (pin "1") (pinfunction "1_1") (pintype "passive"))
      (node (ref "R16") (pin "1") (pintype "passive"))
      (node (ref "U14") (pin "1") (pinfunction "1_1") (pintype "passive"))
      (node (ref "U14") (pin "3") (pinfunction "3_3") (pintype "passive"))
    )
    (net (code "65") (name "Net-(C54-Pad1)") (class "Default")
      (node (ref "C54") (pin "1") (pinfunction "1_1") (pintype "passive"))
      (node (ref "FB2") (pin "1") (pinfunction "1_1") (pintype "passive"))
      (node (ref "R19") (pin "1") (pintype "passive"))
      (node (ref "U9") (pin "1") (pinfunction "1_1") (pintype "passive"))
      (node (ref "U9") (pin "3") (pinfunction "3_3") (pintype "passive"))
    )
    (net (code "66") (name "Net-(D7-A)") (class "Default")
      (node (ref "D7") (pin "1") (pinfunction "A_1") (pintype "passive"))
      (node (ref "K1") (pin "3") (pintype "passive"))
      (node (ref "Q3") (pin "3") (pinfunction "C_3") (pintype "passive"))
    )
    (net (code "67") (name "Net-(D8-A)") (class "Default")
      (node (ref "D8") (pin "1") (pinfunction "A_1") (pintype "passive"))
      (node (ref "K2") (pin "3") (pintype "passive"))
      (node (ref "Q4") (pin "3") (pinfunction "C_3") (pintype "passive"))
    )
    (net (code "68") (name "Net-(D10-A)") (class "Default")
      (node (ref "D10") (pin "1") (pinfunction "A_1") (pintype "passive"))
      (node (ref "K3") (pin "3") (pintype "passive"))
      (node (ref "Q5") (pin "3") (pinfunction "C_3") (pintype "passive"))
    )
    (net (code "69") (name "Net-(DH1-A)") (class "Default")
      (node (ref "CH2") (pin "1") (pintype "passive"))
      (node (ref "CH3") (pin "2") (pinfunction "2_2") (pintype "passive"))
      (node (ref "DH1") (pin "1") (pinfunction "A_1") (pintype "passive"))
      (node (ref "RH9") (pin "2") (pintype "passive"))
      (node (ref "UH3") (pin "3") (pinfunction "+INa_3") (pintype "input"))
    )
    (net (code "70") (name "Net-(DH2-A)") (class "Default")
      (node (ref "DH2") (pin "1") (pinfunction "A_1") (pintype "passive"))
      (node (ref "QH1") (pin "3") (pinfunction "3_3") (pintype "passive"))
      (node (ref "RH8") (pin "2") (pintype "passive"))
      (node (ref "RH9") (pin "1") (pintype "passive"))
    )
    (net (code "71") (name "Net-(DH2-K)") (class "Default")
      (node (ref "DH2") (pin "2") (pinfunction "K_2") (pintype "passive"))
      (node (ref "QH1") (pin "1") (pinfunction "1_1") (pintype "passive"))
      (node (ref "RH7") (pin "2") (pintype "passive"))
    )
    (net (code "72") (name "Net-(DH3-A)") (class "Default")
      (node (ref "CH5") (pin "1") (pintype "passive"))
      (node (ref "CH6") (pin "2") (pinfunction "2_2") (pintype "passive"))
      (node (ref "DH3") (pin "1") (pinfunction "A_1") (pintype "passive"))
      (node (ref "RH18") (pin "2") (pintype "passive"))
      (node (ref "UH3") (pin "5") (pinfunction "+INb_5") (pintype "input"))
    )
    (net (code "73") (name "Net-(DH4-A)") (class "Default")
      (node (ref "DH4") (pin "1") (pinfunction "A_1") (pintype "passive"))
      (node (ref "QH2") (pin "3") (pinfunction "3_3") (pintype "passive"))
      (node (ref "RH17") (pin "2") (pintype "passive"))
      (node (ref "RH18") (pin "1") (pintype "passive"))
    )
    (net (code "74") (name "Net-(DH4-K)") (class "Default")
      (node (ref "DH4") (pin "2") (pinfunction "K_2") (pintype "passive"))
      (node (ref "QH2") (pin "1") (pinfunction "1_1") (pintype "passive"))
      (node (ref "RH16") (pin "2") (pintype "passive"))
    )
    (net (code "75") (name "Net-(J8-Pad3)") (class "Default")
      (node (ref "J8") (pin "3") (pinfunction "3_3") (pintype "passive"))
      (node (ref "R32") (pin "1") (pintype "passive"))
    )
    (net (code "76") (name "Net-(J8-Pad4)") (class "Default")
      (node (ref "J8") (pin "4") (pinfunction "4_4") (pintype "passive"))
      (node (ref "R33") (pin "1") (pintype "passive"))
    )
    (net (code "77") (name "Net-(J8-Pad5)") (class "Default")
      (node (ref "J8") (pin "5") (pinfunction "5_5") (pintype "passive"))
      (node (ref "J8") (pin "6") (pinfunction "6_6") (pintype "passive"))
      (node (ref "R34") (pin "1") (pintype "passive"))
    )
    (net (code "78") (name "Net-(J9-Pad1)") (class "Default")
      (node (ref "J9") (pin "1") (pinfunction "1_1") (pintype "passive"))
      (node (ref "K1") (pin "7") (pintype "passive"))
    )
    (net (code "79") (name "Net-(J9-Pad2)") (class "Default")
      (node (ref "J9") (pin "2") (pinfunction "2_2") (pintype "passive"))
      (node (ref "K1") (pin "1") (pintype "passive"))
    )
    (net (code "80") (name "Net-(J10-Pad1)") (class "Default")
      (node (ref "J10") (pin "1") (pinfunction "1_1") (pintype "passive"))
      (node (ref "K2") (pin "7") (pintype "passive"))
    )
    (net (code "81") (name "Net-(J10-Pad2)") (class "Default")
      (node (ref "J10") (pin "2") (pinfunction "2_2") (pintype "passive"))
      (node (ref "K2") (pin "1") (pintype "passive"))
    )
    (net (code "82") (name "Net-(J11-Pad1)") (class "Default")
      (node (ref "J11") (pin "1") (pinfunction "1_1") (pintype "passive"))
      (node (ref "K3") (pin "7") (pintype "passive"))
    )
    (net (code "83") (name "Net-(J11-Pad2)") (class "Default")
      (node (ref "J11") (pin "2") (pinfunction "2_2") (pintype "passive"))
      (node (ref "K3") (pin "1") (pintype "passive"))
    )
    (net (code "84") (name "Net-(LD2-K)") (class "Default")
      (node (ref "LD2") (pin "2") (pinfunction "K_2") (pintype "passive"))
      (node (ref "R36") (pin "2") (pintype "passive"))
    )
    (net (code "85") (name "Net-(LD3-K)") (class "Default")
      (node (ref "LD3") (pin "2") (pinfunction "K_2") (pintype "passive"))
      (node (ref "R37") (pin "2") (pintype "passive"))
    )
    (net (code "86") (name "Net-(P1-Pad3)") (class "Default")
      (node (ref "P1") (pin "3") (pinfunction "3_3") (pintype "passive"))
      (node (ref "R13") (pin "1") (pintype "passive"))
      (node (ref "R4") (pin "2") (pintype "passive"))
    )
    (net (code "87") (name "Net-(P1-Pad4)") (class "Default")
      (node (ref "P1") (pin "4") (pinfunction "4_4") (pintype "passive"))
      (node (ref "R11") (pin "1") (pintype "passive"))
      (node (ref "R5") (pin "2") (pintype "passive"))
    )
    (net (code "88") (name "Net-(P1-Pad5)") (class "Default")
      (node (ref "P1") (pin "5") (pinfunction "5_5") (pintype "passive"))
      (node (ref "R7") (pin "2") (pintype "passive"))
      (node (ref "R8") (pin "1") (pintype "passive"))
    )
    (net (code "89") (name "Net-(Q3-B)") (class "Default")
      (node (ref "Q3") (pin "1") (pinfunction "B_1") (pintype "passive"))
      (node (ref "R50") (pin "1") (pintype "passive"))
      (node (ref "R51") (pin "1") (pintype "passive"))
    )
    (net (code "90") (name "Net-(Q4-B)") (class "Default")
      (node (ref "Q4") (pin "1") (pinfunction "B_1") (pintype "passive"))
      (node (ref "R53") (pin "1") (pintype "passive"))
      (node (ref "R54") (pin "1") (pintype "passive"))
    )
    (net (code "91") (name "Net-(Q5-B)") (class "Default")
      (node (ref "Q5") (pin "1") (pinfunction "B_1") (pintype "passive"))
      (node (ref "R55") (pin "1") (pintype "passive"))
      (node (ref "R58") (pin "1") (pintype "passive"))
    )
    (net (code "92") (name "Net-(QH1-Pad2)") (class "Default")
      (node (ref "QH1") (pin "2") (pinfunction "2_2") (pintype "passive"))
      (node (ref "RH2") (pin "2") (pintype "passive"))
    )
    (net (code "93") (name "Net-(QH2-Pad2)") (class "Default")
      (node (ref "QH2") (pin "2") (pinfunction "2_2") (pintype "passive"))
      (node (ref "RH12") (pin "2") (pintype "passive"))
    )
    (net (code "94") (name "Net-(R76-Pad2)") (class "Default")
      (node (ref "R76") (pin "2") (pintype "passive"))
      (node (ref "T1") (pin "2") (pinfunction "2_2") (pintype "passive"))
    )
    (net (code "95") (name "Net-(U3-VE2)") (class "Default")
      (node (ref "R23") (pin "1") (pintype "passive"))
      (node (ref "U3") (pin "10") (pinfunction "VE2_10") (pintype "passive"))
    )
    (net (code "96") (name "Net-(U4-C1+)") (class "Default")
      (node (ref "C26") (pin "1") (pinfunction "1_1") (pintype "passive"))
      (node (ref "U4") (pin "1") (pinfunction "C1+_1") (pintype "passive"))
    )
    (net (code "97") (name "Net-(U4-C1-)") (class "Default")
      (node (ref "C26") (pin "2") (pinfunction "2_2") (pintype "passive"))
      (node (ref "U4") (pin "3") (pinfunction "C1-_3") (pintype "passive"))
    )
    (net (code "98") (name "Net-(U4-C2+)") (class "Default")
      (node (ref "C39") (pin "2") (pinfunction "2_2") (pintype "passive"))
      (node (ref "U4") (pin "4") (pinfunction "C2+_4") (pintype "passive"))
    )
    (net (code "99") (name "Net-(U4-C2-)") (class "Default")
      (node (ref "C39") (pin "1") (pinfunction "1_1") (pintype "passive"))
      (node (ref "U4") (pin "5") (pinfunction "C2-_5") (pintype "passive"))
    )
    (net (code "100") (name "Net-(U4-V+)") (class "Default")
      (node (ref "C28") (pin "1") (pinfunction "1_1") (pintype "passive"))
      (node (ref "U4") (pin "2") (pinfunction "V+_2") (pintype "passive"))
    )
    (net (code "101") (name "Net-(U4-V-)") (class "Default")
      (node (ref "C40") (pin "1") (pinfunction "1_1") (pintype "passive"))
      (node (ref "U4") (pin "6") (pinfunction "V-_6") (pintype "passive"))
    )
    (net (code "102") (name "Net-(U5-AIN1(+))") (class "Default")
      (node (ref "C29") (pin "2") (pinfunction "2_2") (pintype "passive"))
      (node (ref "C30") (pin "1") (pinfunction "1_1") (pintype "passive"))
      (node (ref "R20") (pin "2") (pintype "passive"))
      (node (ref "U5") (pin "5") (pinfunction "AIN1(+)_5") (pintype "passive"))
    )
    (net (code "103") (name "Net-(U5-AIN1(-))") (class "Default")
      (node (ref "C30") (pin "2") (pinfunction "2_2") (pintype "passive"))
      (node (ref "C31") (pin "1") (pinfunction "1_1") (pintype "passive"))
      (node (ref "R25") (pin "2") (pintype "passive"))
      (node (ref "U5") (pin "6") (pinfunction "AIN1(-)_6") (pintype "passive"))
    )
    (net (code "104") (name "Net-(U5-AIN2(+))") (class "Default")
      (node (ref "C17") (pin "1") (pintype "passive"))
      (node (ref "R3") (pin "2") (pintype "passive"))
      (node (ref "U5") (pin "7") (pinfunction "AIN2(+)_7") (pintype "passive"))
    )
    (net (code "105") (name "Net-(U5-IOUT2)") (class "Default")
      (node (ref "R2") (pin "2") (pintype "passive"))
      (node (ref "U5") (pin "11") (pinfunction "IOUT2_11") (pintype "passive"))
    )
    (net (code "106") (name "Net-(U12-A)") (class "Default")
      (node (ref "F10") (pin "1") (pinfunction "1_1") (pintype "passive"))
      (node (ref "R41") (pin "2") (pintype "passive"))
      (node (ref "T1") (pin "1") (pinfunction "1_1") (pintype "passive"))
      (node (ref "U12") (pin "13") (pinfunction "Y_13") (pintype "passive"))
      (node (ref "U12") (pin "18") (pinfunction "A_18") (pintype "passive"))
      (node (ref "ZD14") (pin "1") (pintype "passive"))
      (node (ref "ZD15") (pin "1") (pintype "passive"))
    )
    (net (code "107") (name "Net-(U12-B)") (class "Default")
      (node (ref "F11") (pin "1") (pinfunction "1_1") (pintype "passive"))
      (node (ref "R42") (pin "1") (pintype "passive"))
      (node (ref "R76") (pin "1") (pintype "passive"))
      (node (ref "U12") (pin "15") (pinfunction "Z_15") (pintype "passive"))
      (node (ref "U12") (pin "17") (pinfunction "B_17") (pintype "passive"))
      (node (ref "ZD14") (pin "2") (pintype "passive"))
      (node (ref "ZD16") (pin "2") (pintype "passive"))
    )
    (net (code "108") (name "Net-(U13-VE2)") (class "Default")
      (node (ref "R71") (pin "2") (pintype "passive"))
      (node (ref "U13") (pin "10") (pinfunction "VE2_10") (pintype "passive"))
    )
    (net (code "109") (name "Net-(U15-INP)") (class "Default")
      (node (ref "R24") (pin "2") (pintype "passive"))
      (node (ref "U15") (pin "5") (pinfunction "INP_5") (pintype "input"))
    )
    (net (code "110") (name "Net-(U15-VOCM)") (class "Default")
      (node (ref "R25") (pin "1") (pintype "passive"))
      (node (ref "U15") (pin "11") (pinfunction "VOCM_11") (pintype "output"))
    )
    (net (code "111") (name "Net-(U15-VOut)") (class "Default")
      (node (ref "R20") (pin "1") (pintype "passive"))
      (node (ref "U15") (pin "12") (pinfunction "VOut_12") (pintype "output"))
    )
    (net (code "112") (name "Net-(UH1A-+INa)") (class "Default")
      (node (ref "CH1") (pin "2") (pinfunction "2_2") (pintype "passive"))
      (node (ref "RH1") (pin "1") (pintype "passive"))
      (node (ref "UH1") (pin "3") (pinfunction "+INa_3") (pintype "input"))
    )
    (net (code "113") (name "Net-(UH1A-+V)") (class "Default")
      (node (ref "RH3") (pin "2") (pintype "passive"))
      (node (ref "UH1") (pin "8") (pinfunction "+V_8") (pintype "power_in"))
    )
    (net (code "114") (name "Net-(UH1A--INa)") (class "Default")
      (node (ref "RH6") (pin "2") (pintype "passive"))
      (node (ref "UH1") (pin "1") (pinfunction "Oa_1") (pintype "output"))
      (node (ref "UH1") (pin "2") (pinfunction "-INa_2") (pintype "input"))
    )
    (net (code "115") (name "Net-(UH1B-+INb)") (class "Default")
      (node (ref "RH4") (pin "1") (pintype "passive"))
      (node (ref "RH6") (pin "1") (pintype "passive"))
      (node (ref "UH1") (pin "5") (pinfunction "+INb_5") (pintype "input"))
    )
    (net (code "116") (name "Net-(UH1B--INb)") (class "Default")
      (node (ref "RH10") (pin "1") (pintype "passive"))
      (node (ref "RH8") (pin "1") (pintype "passive"))
      (node (ref "UH1") (pin "6") (pinfunction "-INb_6") (pintype "input"))
    )
    (net (code "117") (name "Net-(UH1B-Ob)") (class "Default")
      (node (ref "RH7") (pin "1") (pintype "passive"))
      (node (ref "UH1") (pin "7") (pinfunction "Ob_7") (pintype "output"))
    )
    (net (code "118") (name "Net-(UH2A-+INa)") (class "Default")
      (node (ref "CH4") (pin "2") (pinfunction "2_2") (pintype "passive"))
      (node (ref "RH11") (pin "1") (pintype "passive"))
      (node (ref "UH2") (pin "3") (pinfunction "+INa_3") (pintype "input"))
    )
    (net (code "119") (name "Net-(UH2A-+V)") (class "Default")
      (node (ref "RH13") (pin "2") (pintype "passive"))
      (node (ref "UH2") (pin "8") (pinfunction "+V_8") (pintype "power_in"))
    )
    (net (code "120") (name "Net-(UH2A--INa)") (class "Default")
      (node (ref "RH15") (pin "2") (pintype "passive"))
      (node (ref "UH2") (pin "1") (pinfunction "Oa_1") (pintype "output"))
      (node (ref "UH2") (pin "2") (pinfunction "-INa_2") (pintype "input"))
    )
    (net (code "121") (name "Net-(UH2B-+INb)") (class "Default")
      (node (ref "RH14") (pin "1") (pintype "passive"))
      (node (ref "RH15") (pin "1") (pintype "passive"))
      (node (ref "UH2") (pin "5") (pinfunction "+INb_5") (pintype "input"))
    )
    (net (code "122") (name "Net-(UH2B--INb)") (class "Default")
      (node (ref "RH17") (pin "1") (pintype "passive"))
      (node (ref "RH19") (pin "1") (pintype "passive"))
      (node (ref "UH2") (pin "6") (pinfunction "-INb_6") (pintype "input"))
    )
    (net (code "123") (name "Net-(UH2B-Ob)") (class "Default")
      (node (ref "RH16") (pin "1") (pintype "passive"))
      (node (ref "UH2") (pin "7") (pinfunction "Ob_7") (pintype "output"))
    )
    (net (code "124") (name "Net-(UH3A-+V)") (class "Default")
      (node (ref "RH5") (pin "2") (pintype "passive"))
      (node (ref "UH3") (pin "8") (pinfunction "+V_8") (pintype "power_in"))
    )
    (net (code "125") (name "Net-(UH3A--INa)") (class "Default")
      (node (ref "RH4") (pin "2") (pintype "passive"))
      (node (ref "UH3") (pin "1") (pinfunction "Oa_1") (pintype "output"))
      (node (ref "UH3") (pin "2") (pinfunction "-INa_2") (pintype "input"))
    )
    (net (code "126") (name "Net-(UH3B--INb)") (class "Default")
      (node (ref "RH14") (pin "2") (pintype "passive"))
      (node (ref "UH3") (pin "6") (pinfunction "-INb_6") (pintype "input"))
      (node (ref "UH3") (pin "7") (pinfunction "Ob_7") (pintype "output"))
    )
    (net (code "127") (name "REF2.5V") (class "Default")
      (node (ref "C33") (pin "1") (pinfunction "1_1") (pintype "passive"))
      (node (ref "C34") (pin "1") (pintype "passive"))
      (node (ref "C35") (pin "1") (pinfunction "1_1") (pintype "passive"))
      (node (ref "FB6") (pin "2") (pinfunction "2_2") (pintype "passive"))
      (node (ref "U15") (pin "9") (pinfunction "VREF_9") (pintype "input"))
      (node (ref "U5") (pin "9") (pinfunction "REFIN(+)/AIN3(+)_9") (pintype "passive"))
    )
    (net (code "128") (name "V330_D") (class "Default")
      (node (ref "C1") (pin "1") (pintype "passive"))
      (node (ref "C27") (pin "2") (pinfunction "2_2") (pintype "passive"))
      (node (ref "C4") (pin "2") (pinfunction "2_2") (pintype "passive"))
      (node (ref "C43") (pin "1") (pintype "passive"))
      (node (ref "C44") (pin "1") (pintype "passive"))
      (node (ref "C56") (pin "1") (pinfunction "1_1") (pintype "passive"))
      (node (ref "C9") (pin "2") (pintype "passive"))
      (node (ref "CA1") (pin "1") (pintype "passive"))
      (node (ref "CA13") (pin "1") (pintype "passive"))
      (node (ref "CA14") (pin "1") (pintype "passive"))
      (node (ref "CA4") (pin "1") (pintype "passive"))
      (node (ref "D6") (pin "2") (pinfunction "K_2") (pintype "passive"))
      (node (ref "J21") (pin "1") (pinfunction "1_1") (pintype "passive"))
      (node (ref "J21") (pin "2") (pinfunction "2_2") (pintype "passive"))
      (node (ref "J7") (pin "4") (pinfunction "4_4") (pintype "passive"))
      (node (ref "LD2") (pin "1") (pinfunction "A_1") (pintype "passive"))
      (node (ref "LD3") (pin "1") (pinfunction "A_1") (pintype "passive"))
      (node (ref "P1") (pin "1") (pinfunction "1_1") (pintype "passive"))
      (node (ref "PQ1") (pin "1") (pinfunction "C_1") (pintype "passive"))
      (node (ref "R1") (pin "2") (pintype "passive"))
      (node (ref "R14") (pin "2") (pintype "passive"))
      (node (ref "R15") (pin "2") (pintype "passive"))
      (node (ref "R17") (pin "2") (pintype "passive"))
      (node (ref "R26") (pin "2") (pintype "passive"))
      (node (ref "R30") (pin "2") (pintype "passive"))
      (node (ref "R35") (pin "1") (pintype "passive"))
      (node (ref "R40") (pin "1") (pintype "passive"))
      (node (ref "R43") (pin "1") (pintype "passive"))
      (node (ref "R44") (pin "1") (pintype "passive"))
      (node (ref "R59") (pin "2") (pintype "passive"))
      (node (ref "R60") (pin "2") (pintype "passive"))
      (node (ref "R61") (pin "2") (pintype "passive"))
      (node (ref "R62") (pin "2") (pintype "passive"))
      (node (ref "R63") (pin "2") (pintype "passive"))
      (node (ref "U12") (pin "2") (pinfunction "VCC_2") (pintype "passive"))
      (node (ref "U12") (pin "8") (pinfunction "VCC_8") (pintype "passive"))
      (node (ref "U13") (pin "1") (pinfunction "VDD1_1") (pintype "passive"))
      (node (ref "U3") (pin "1") (pinfunction "VDD1_1") (pintype "passive"))
      (node (ref "U4") (pin "16") (pinfunction "VDD_16") (pintype "passive"))
    )
    (net (code "129") (name "V500_A") (class "Default")
      (node (ref "FB5") (pin "2") (pinfunction "2_2") (pintype "passive"))
    )
    (net (code "130") (name "VA_ISO") (class "Default")
      (node (ref "C5") (pin "1") (pinfunction "1_1") (pintype "passive"))
      (node (ref "C53") (pin "1") (pinfunction "1_1") (pintype "passive"))
      (node (ref "C57") (pin "1") (pinfunction "1_1") (pintype "passive"))
      (node (ref "CA5") (pin "1") (pintype "passive"))
      (node (ref "R19") (pin "2") (pintype "passive"))
      (node (ref "R71") (pin "1") (pintype "passive"))
      (node (ref "U13") (pin "16") (pinfunction "VDD2_16") (pintype "passive"))
      (node (ref "U2") (pin "6") (pinfunction "VCC_6") (pintype "power_in"))
    )
    (net (code "131") (name "VDD_ISO") (class "Default")
      (node (ref "C24") (pin "1") (pintype "passive"))
      (node (ref "C25") (pin "1") (pinfunction "1_1") (pintype "passive"))
      (node (ref "C38") (pin "1") (pinfunction "1_1") (pintype "passive"))
      (node (ref "C8") (pin "1") (pintype "passive"))
      (node (ref "CA2") (pin "1") (pintype "passive"))
      (node (ref "FB1") (pin "1") (pinfunction "1_1") (pintype "passive"))
      (node (ref "R16") (pin "2") (pintype "passive"))
      (node (ref "R23") (pin "2") (pintype "passive"))
      (node (ref "U15") (pin "1") (pinfunction "VDD_1") (pintype "power_in"))
      (node (ref "U15") (pin "14") (pinfunction "CSB_14") (pintype "input"))
      (node (ref "U3") (pin "16") (pinfunction "VDD2_16") (pintype "passive"))
      (node (ref "U5") (pin "13") (pinfunction "AVDD_13") (pintype "passive"))
    )
    (net (code "132") (name "unconnected-(J1-Pad2)") (class "Default")
      (node (ref "J1") (pin "2") (pinfunction "2_2") (pintype "passive+no_connect"))
    )
    (net (code "133") (name "unconnected-(J4-Pad3)") (class "Default")
      (node (ref "J4") (pin "3") (pinfunction "3_3") (pintype "passive"))
    )
    (net (code "134") (name "unconnected-(J7-Pad1)") (class "Default")
      (node (ref "J7") (pin "1") (pinfunction "1_1") (pintype "passive+no_connect"))
    )
    (net (code "135") (name "unconnected-(J7-Pad8)") (class "Default")
      (node (ref "J7") (pin "8") (pinfunction "8_8") (pintype "passive+no_connect"))
    )
    (net (code "136") (name "unconnected-(J13-Pad1)") (class "Default")
      (node (ref "J13") (pin "1") (pinfunction "1_1") (pintype "passive"))
    )
    (net (code "137") (name "unconnected-(J13-Pad2)") (class "Default")
      (node (ref "J13") (pin "2") (pinfunction "2_2") (pintype "passive"))
    )
    (net (code "138") (name "unconnected-(J13-Pad3)") (class "Default")
      (node (ref "J13") (pin "3") (pinfunction "3_3") (pintype "passive"))
    )
    (net (code "139") (name "unconnected-(J13-Pad4)") (class "Default")
      (node (ref "J13") (pin "4") (pinfunction "4_4") (pintype "passive"))
    )
    (net (code "140") (name "unconnected-(J13-Pad5)") (class "Default")
      (node (ref "J13") (pin "5") (pinfunction "5_5") (pintype "passive"))
    )
    (net (code "141") (name "unconnected-(J13-Pad6)") (class "Default")
      (node (ref "J13") (pin "6") (pinfunction "6_6") (pintype "passive"))
    )
    (net (code "142") (name "unconnected-(P3-Pad2)") (class "Default")
      (node (ref "P3") (pin "2") (pinfunction "2_2") (pintype "passive+no_connect"))
    )
    (net (code "143") (name "unconnected-(U3-VE1-Pad7)") (class "Default")
      (node (ref "U3") (pin "7") (pinfunction "VE1_7") (pintype "passive+no_connect"))
    )
    (net (code "144") (name "unconnected-(U4-R2in-Pad8)") (class "Default")
      (node (ref "U4") (pin "8") (pinfunction "R2in_8") (pintype "passive+no_connect"))
    )
    (net (code "145") (name "unconnected-(U4-R2out-Pad9)") (class "Default")
      (node (ref "U4") (pin "9") (pinfunction "R2out_9") (pintype "passive+no_connect"))
    )
    (net (code "146") (name "unconnected-(U4-T2in-Pad10)") (class "Default")
      (node (ref "U4") (pin "10") (pinfunction "T2in_10") (pintype "passive+no_connect"))
    )
    (net (code "147") (name "unconnected-(U4-T2out-Pad7)") (class "Default")
      (node (ref "U4") (pin "7") (pinfunction "T2out_7") (pintype "passive+no_connect"))
    )
    (net (code "148") (name "unconnected-(U5-CLK-Pad2)") (class "Default")
      (node (ref "U5") (pin "2") (pinfunction "CLK_2") (pintype "passive+no_connect"))
    )
    (net (code "149") (name "unconnected-(U5-IOUT1-Pad4)") (class "Default")
      (node (ref "U5") (pin "4") (pinfunction "IOUT1_4") (pintype "passive"))
    )
    (net (code "150") (name "unconnected-(U13-VE1-Pad7)") (class "Default")
      (node (ref "U13") (pin "7") (pinfunction "VE1_7") (pintype "passive+no_connect"))
    )
    (net (code "151") (name "unconnected-(U13-VID-Pad11)") (class "Default")
      (node (ref "U13") (pin "11") (pinfunction "VID_11") (pintype "passive"))
    )
    (net (code "152") (name "unconnected-(U13-VOD-Pad6)") (class "Default")
      (node (ref "U13") (pin "6") (pinfunction "VOD_6") (pintype "passive"))
    )
    (net (code "153") (name "unconnected-(U15-CAL-Pad2)") (class "Default")
      (node (ref "U15") (pin "2") (pinfunction "CAL_2") (pintype "input+no_connect"))
    )
    (net (code "154") (name "unconnected-(U15-GD2-Pad6)") (class "Default")
      (node (ref "U15") (pin "6") (pinfunction "GD2_6") (pintype "input+no_connect"))
    )
    (net (code "155") (name "unconnected-(U15-RTD-Pad3)") (class "Default")
      (node (ref "U15") (pin "3") (pinfunction "RTD_3") (pintype "input+no_connect"))
    )
    (net (code "156") (name "unconnected-(U15-VCMHI-Pad7)") (class "Default")
      (node (ref "U15") (pin "7") (pinfunction "VCMHI_7") (pintype "input+no_connect"))
    )
    (net (code "157") (name "unconnected-(UH1B-+V-Pad8)") (class "Default")
      (node (ref "UH1") (pin "8") (pinfunction "+V_8") (pintype "power_in"))
    )
    (net (code "158") (name "unconnected-(UH1B--V-Pad4)") (class "Default")
      (node (ref "UH1") (pin "4") (pinfunction "-V_4") (pintype "power_in"))
    )
    (net (code "159") (name "unconnected-(UH2B-+V-Pad8)") (class "Default")
      (node (ref "UH2") (pin "8") (pinfunction "+V_8") (pintype "power_in"))
    )
    (net (code "160") (name "unconnected-(UH2B--V-Pad4)") (class "Default")
      (node (ref "UH2") (pin "4") (pinfunction "-V_4") (pintype "power_in"))
    )
    (net (code "161") (name "unconnected-(UH3B-+V-Pad8)") (class "Default")
      (node (ref "UH3") (pin "8") (pinfunction "+V_8") (pintype "power_in"))
    )
    (net (code "162") (name "unconnected-(UH3B--V-Pad4)") (class "Default")
      (node (ref "UH3") (pin "4") (pinfunction "-V_4") (pintype "power_in"))
    )
  )
)
